# Amplificador_Logaritmo.net
KiCad netlist of a schematic drawn in EasyEDA Pro
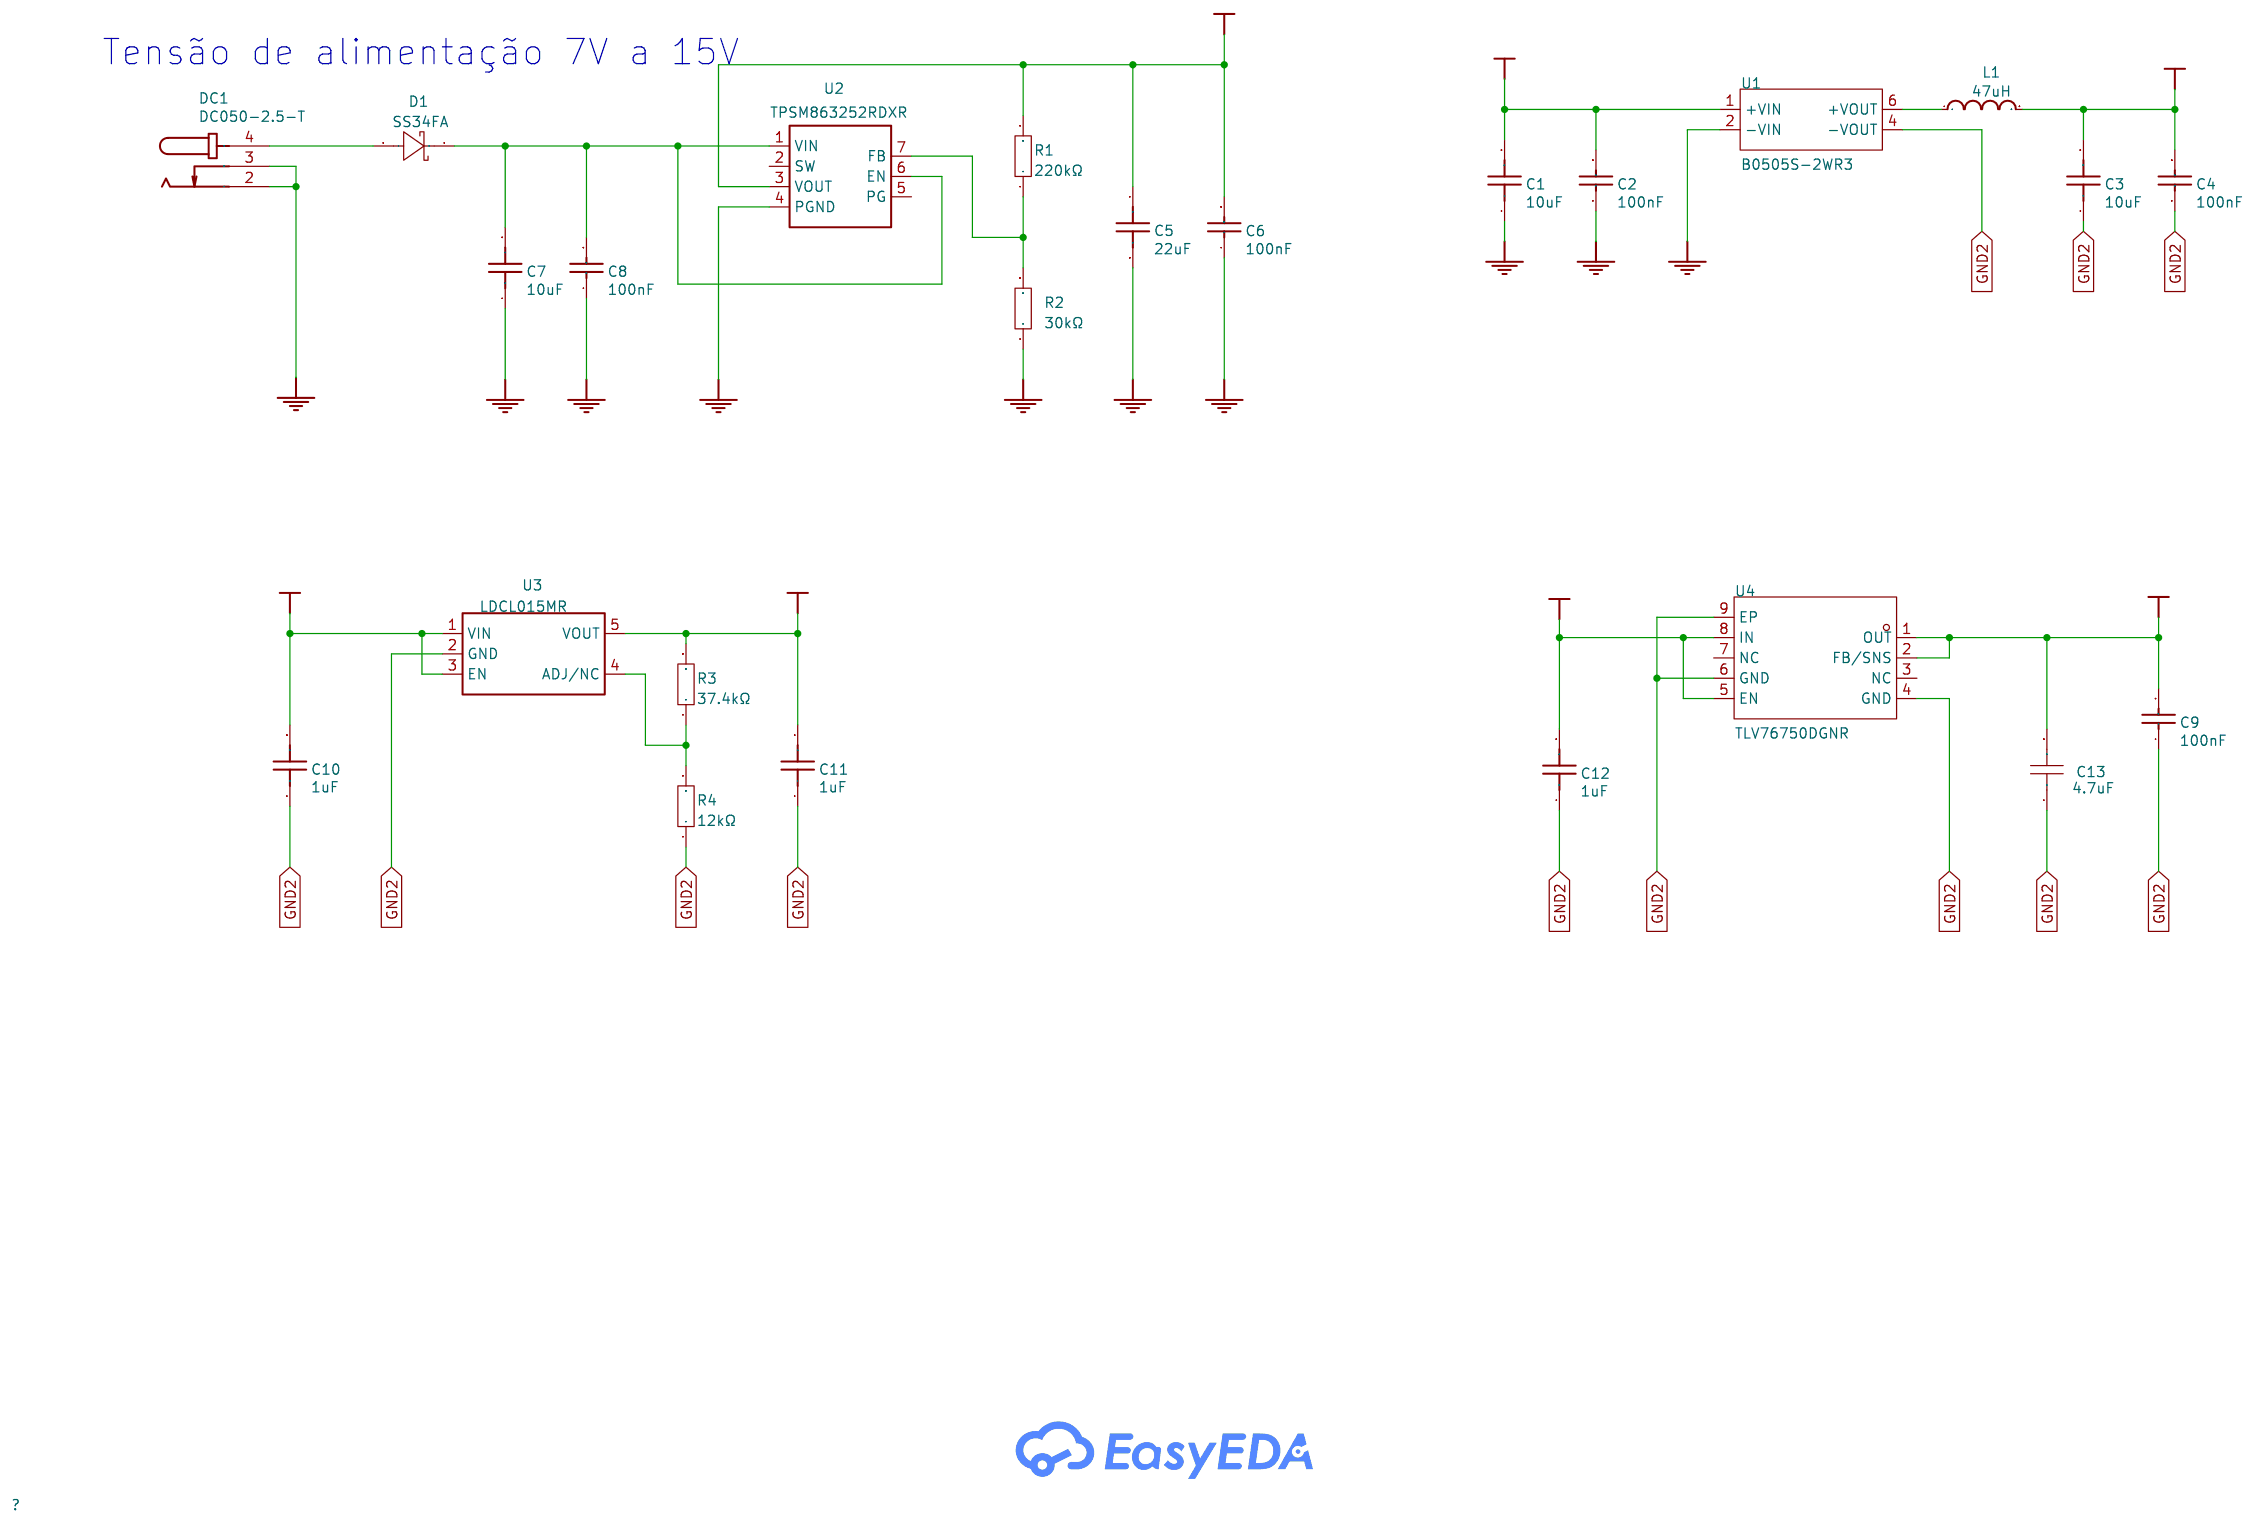
[diagram p0: Fontes]
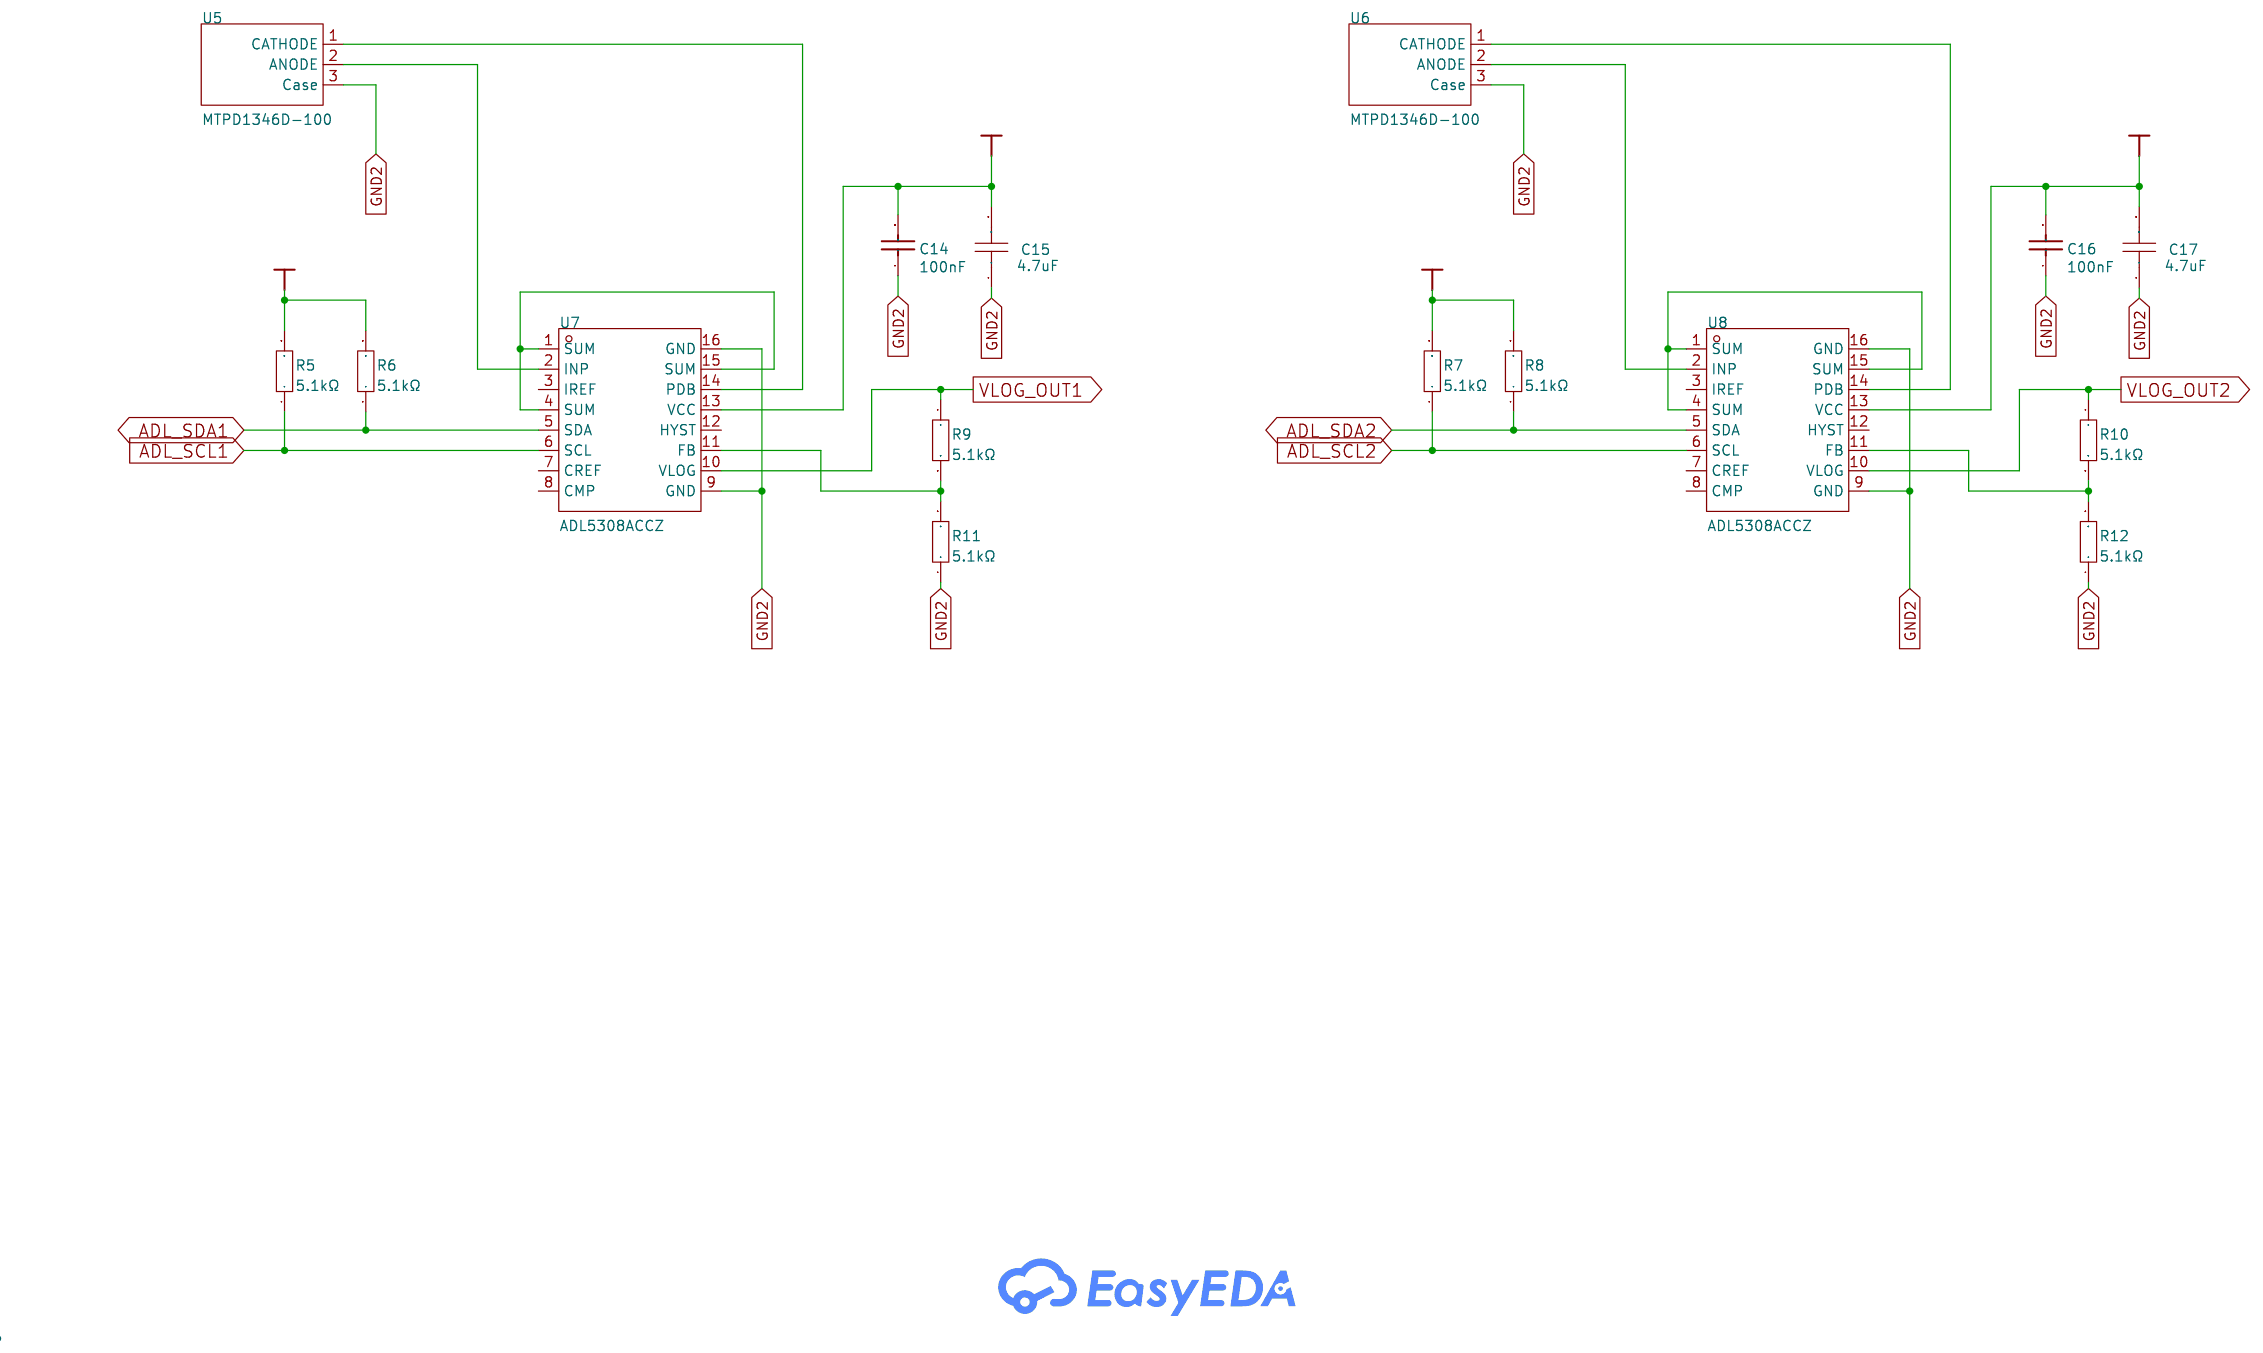
[diagram p1: Amplificador 1 e 2]
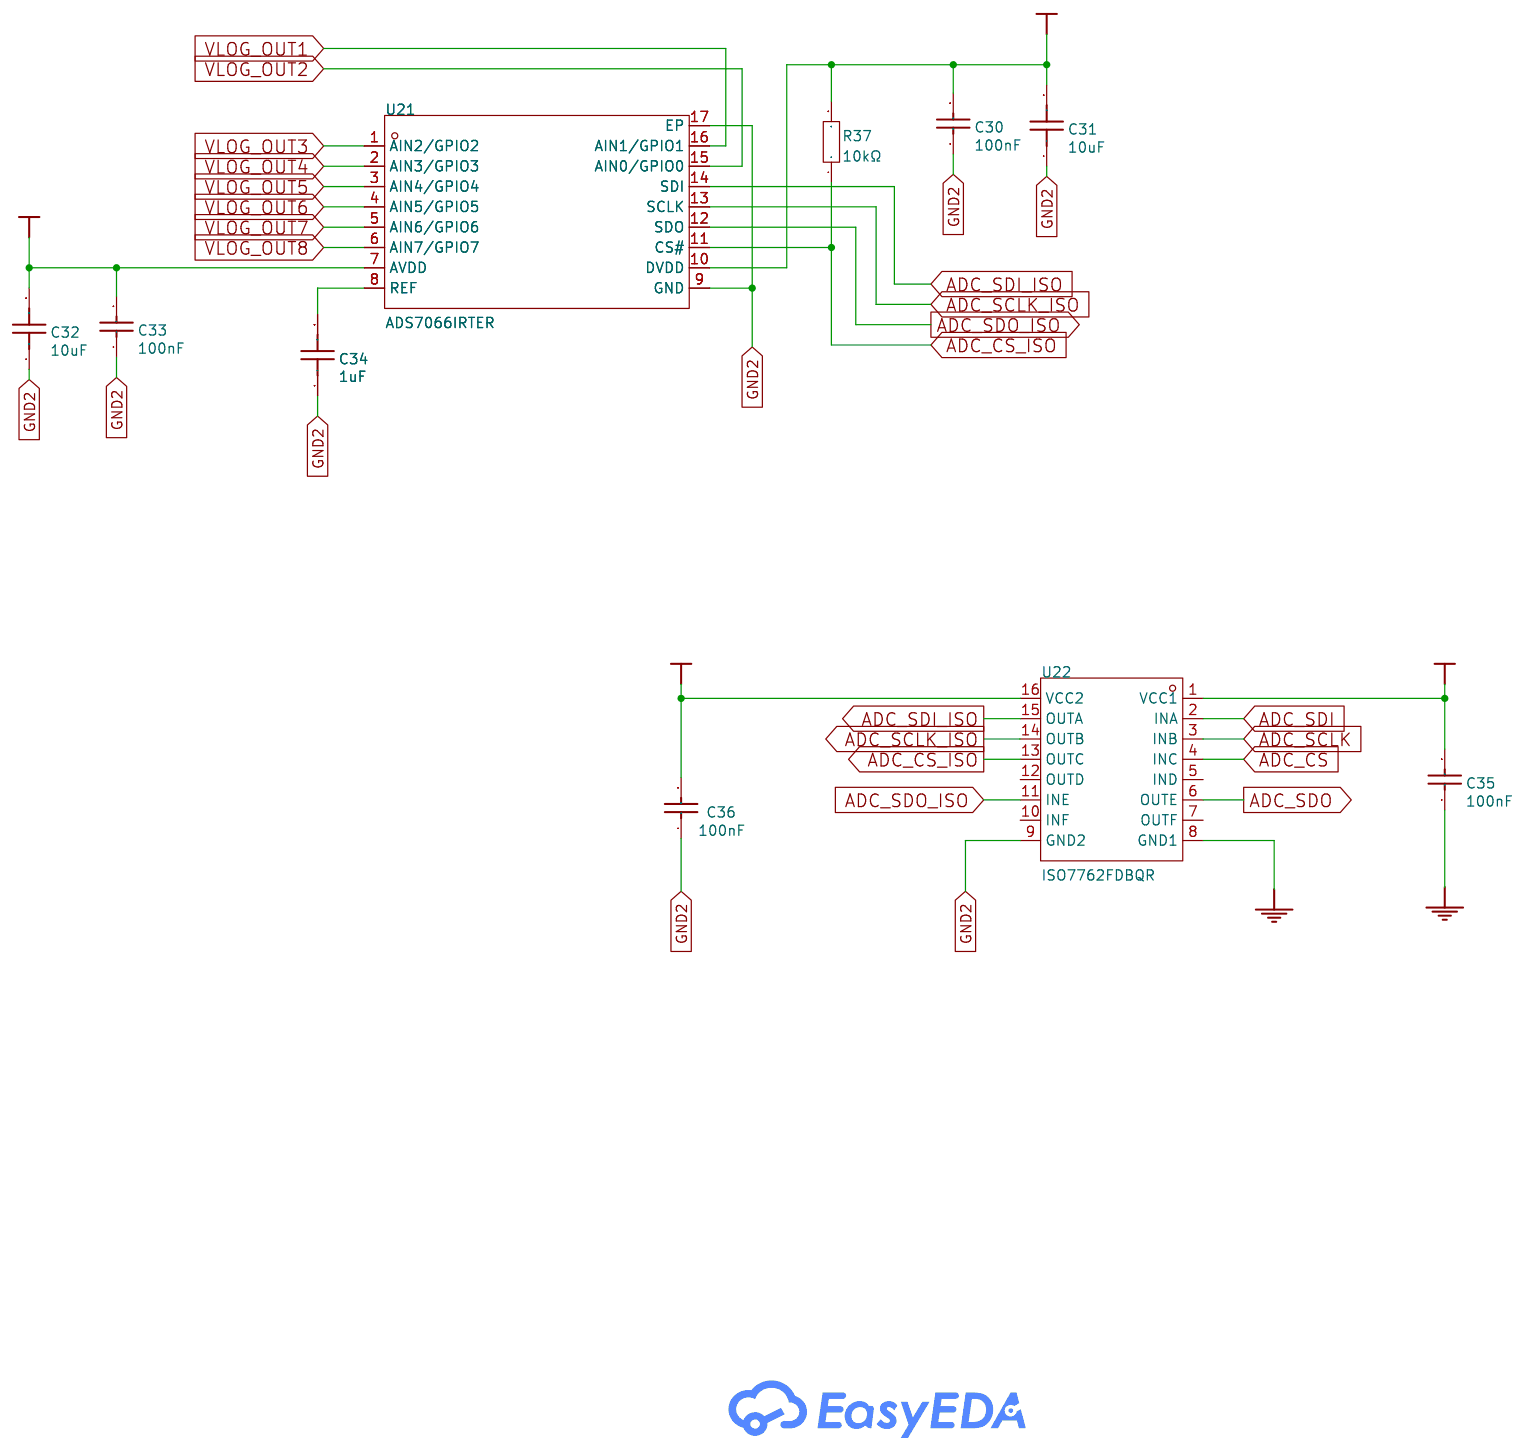
[diagram p2: ADC]
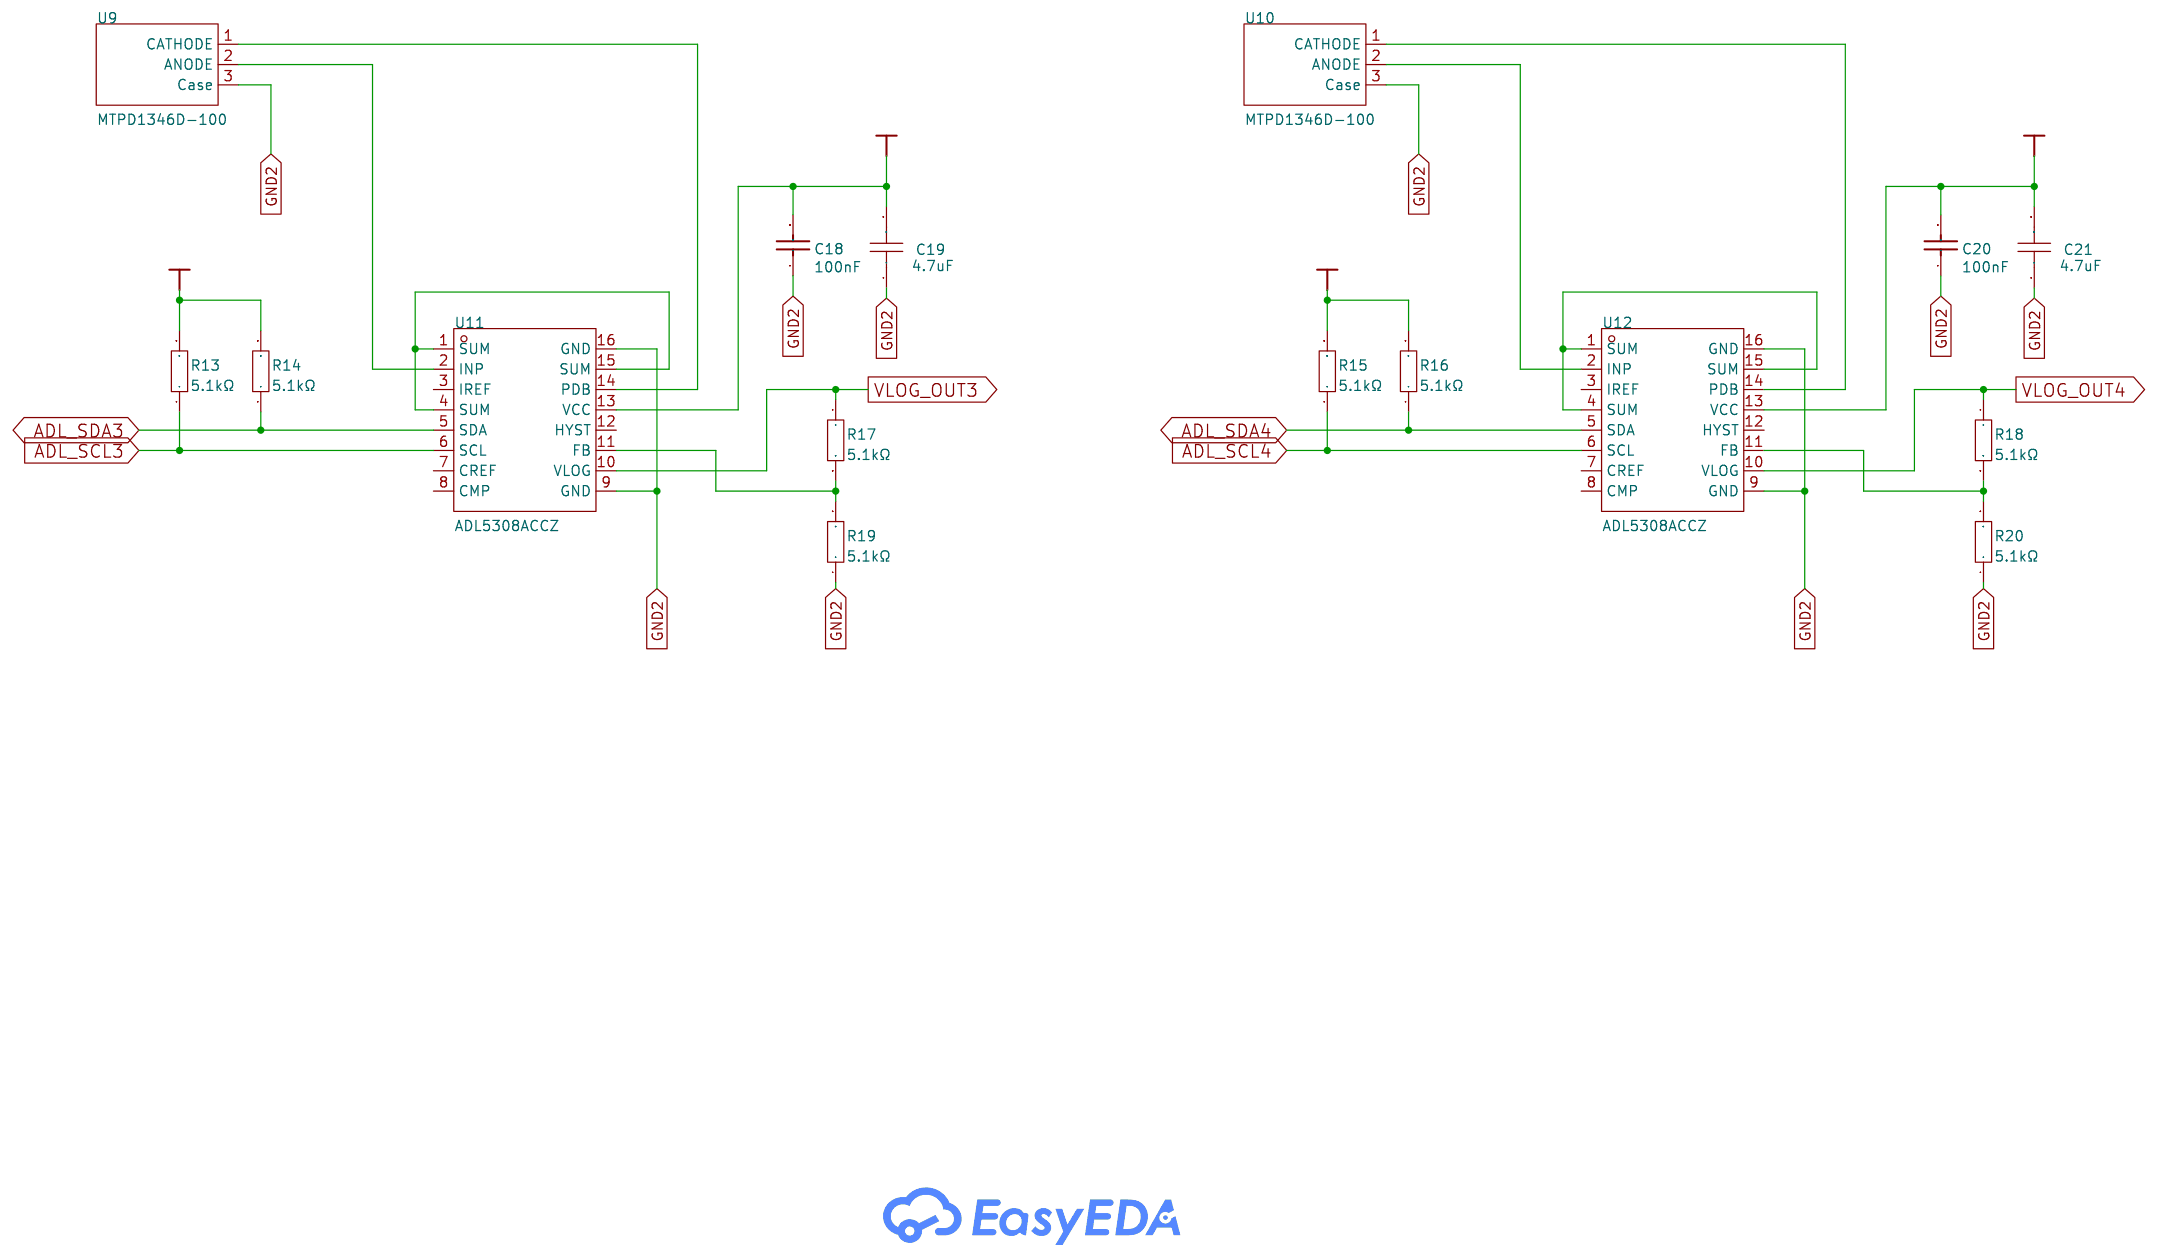
[diagram p3: Amplificador 3 e 4]
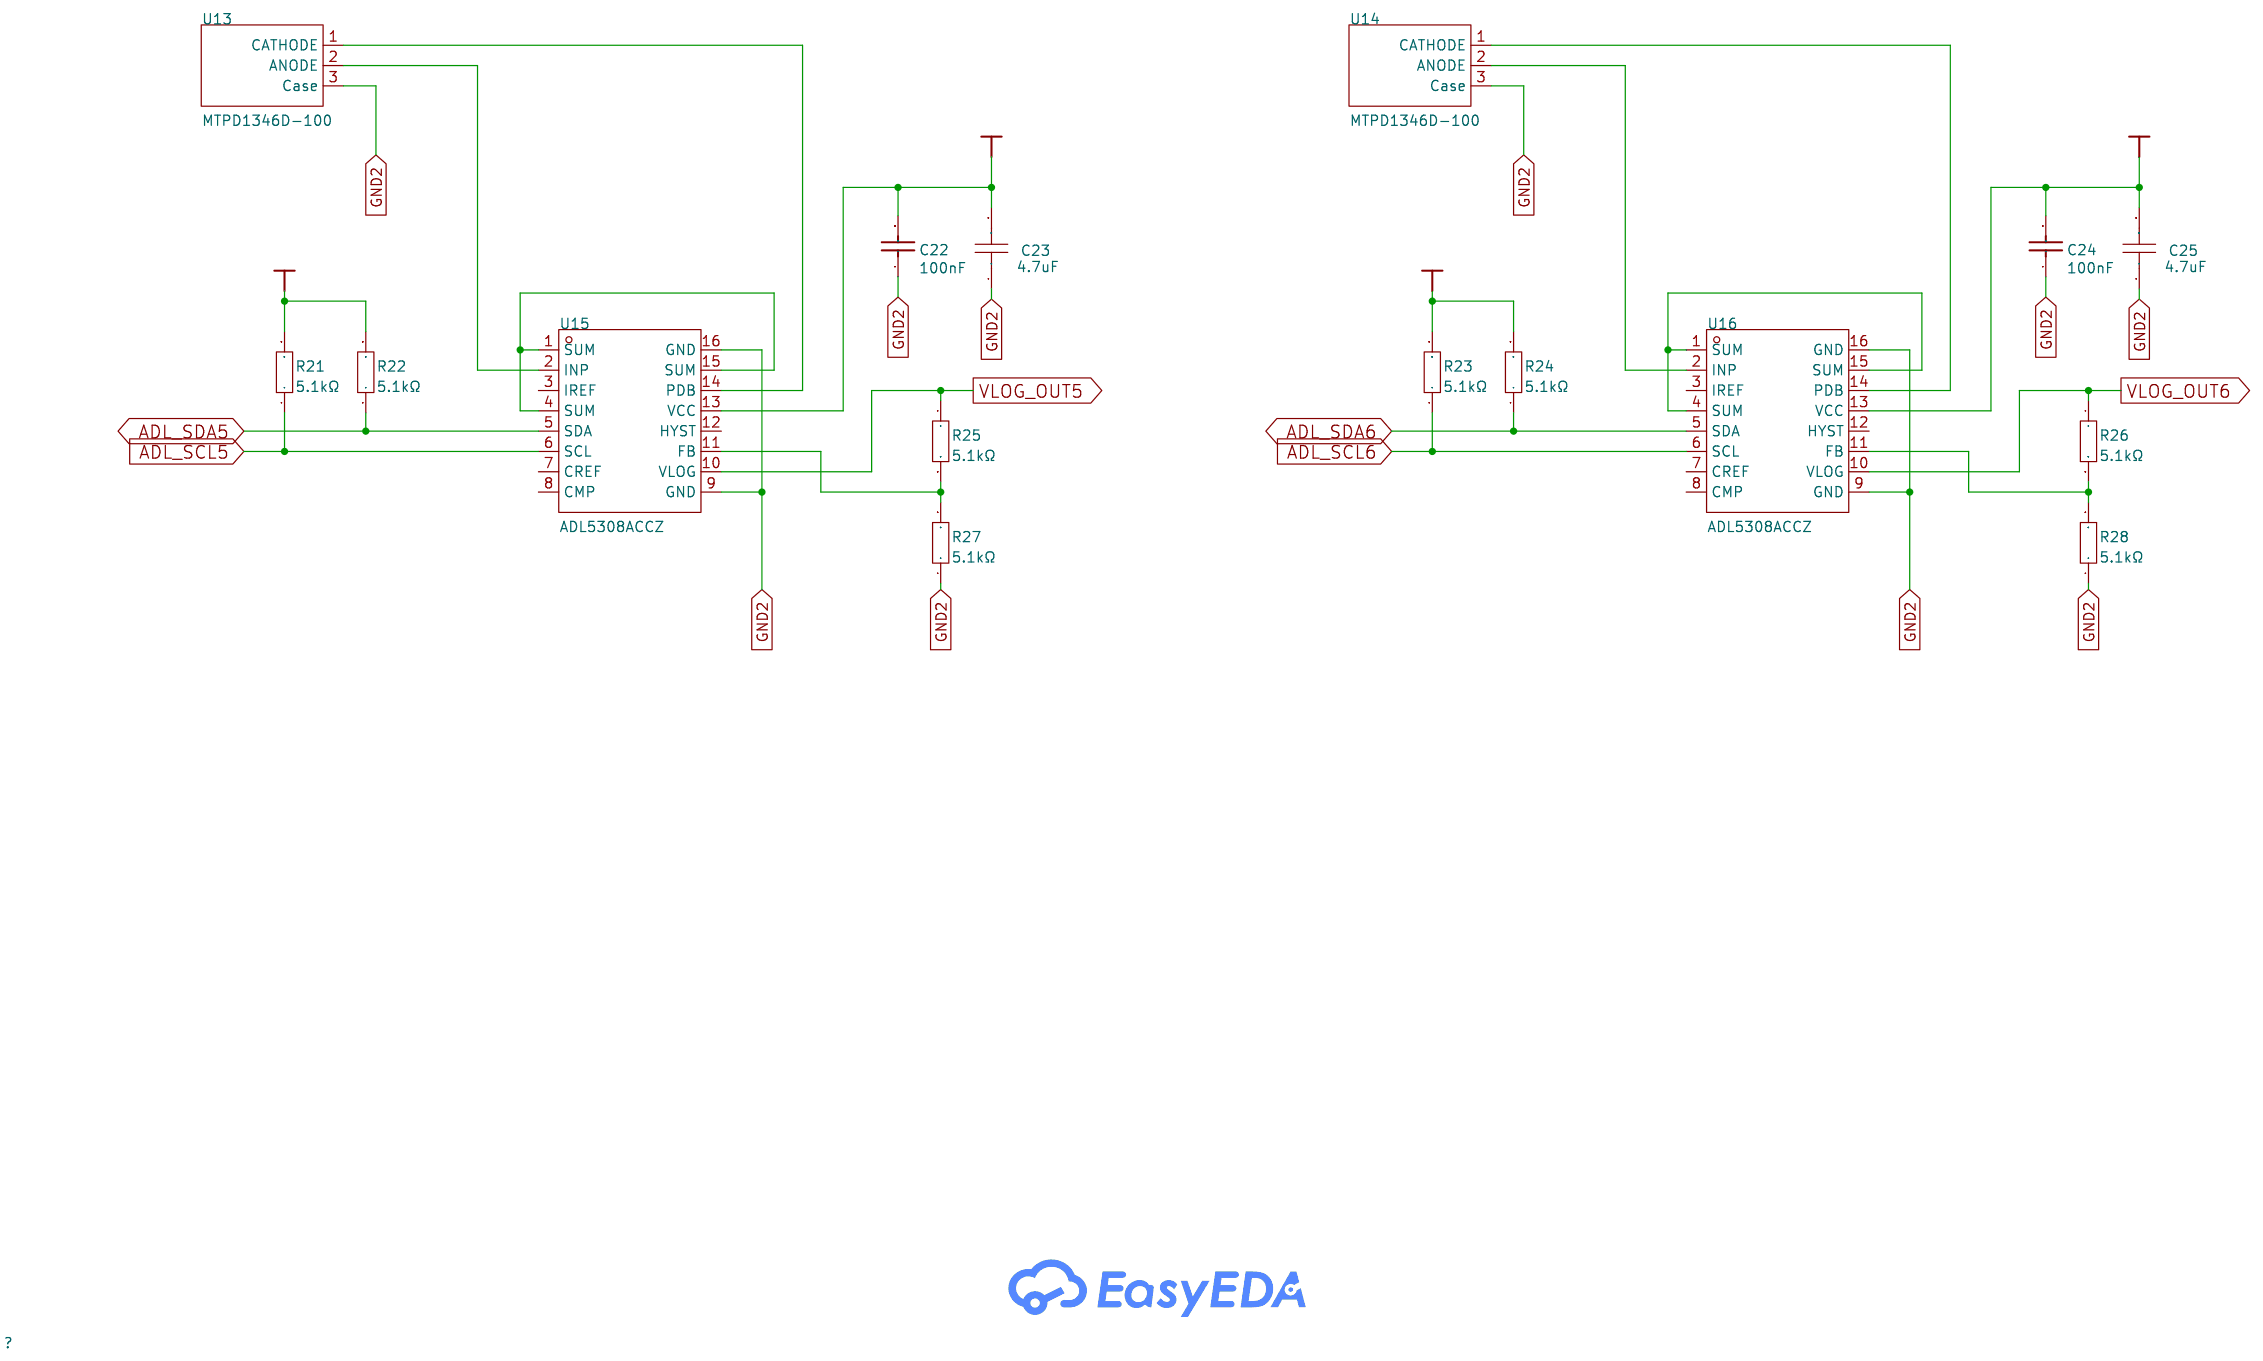
[diagram p4: Amplificador 5 e 6]
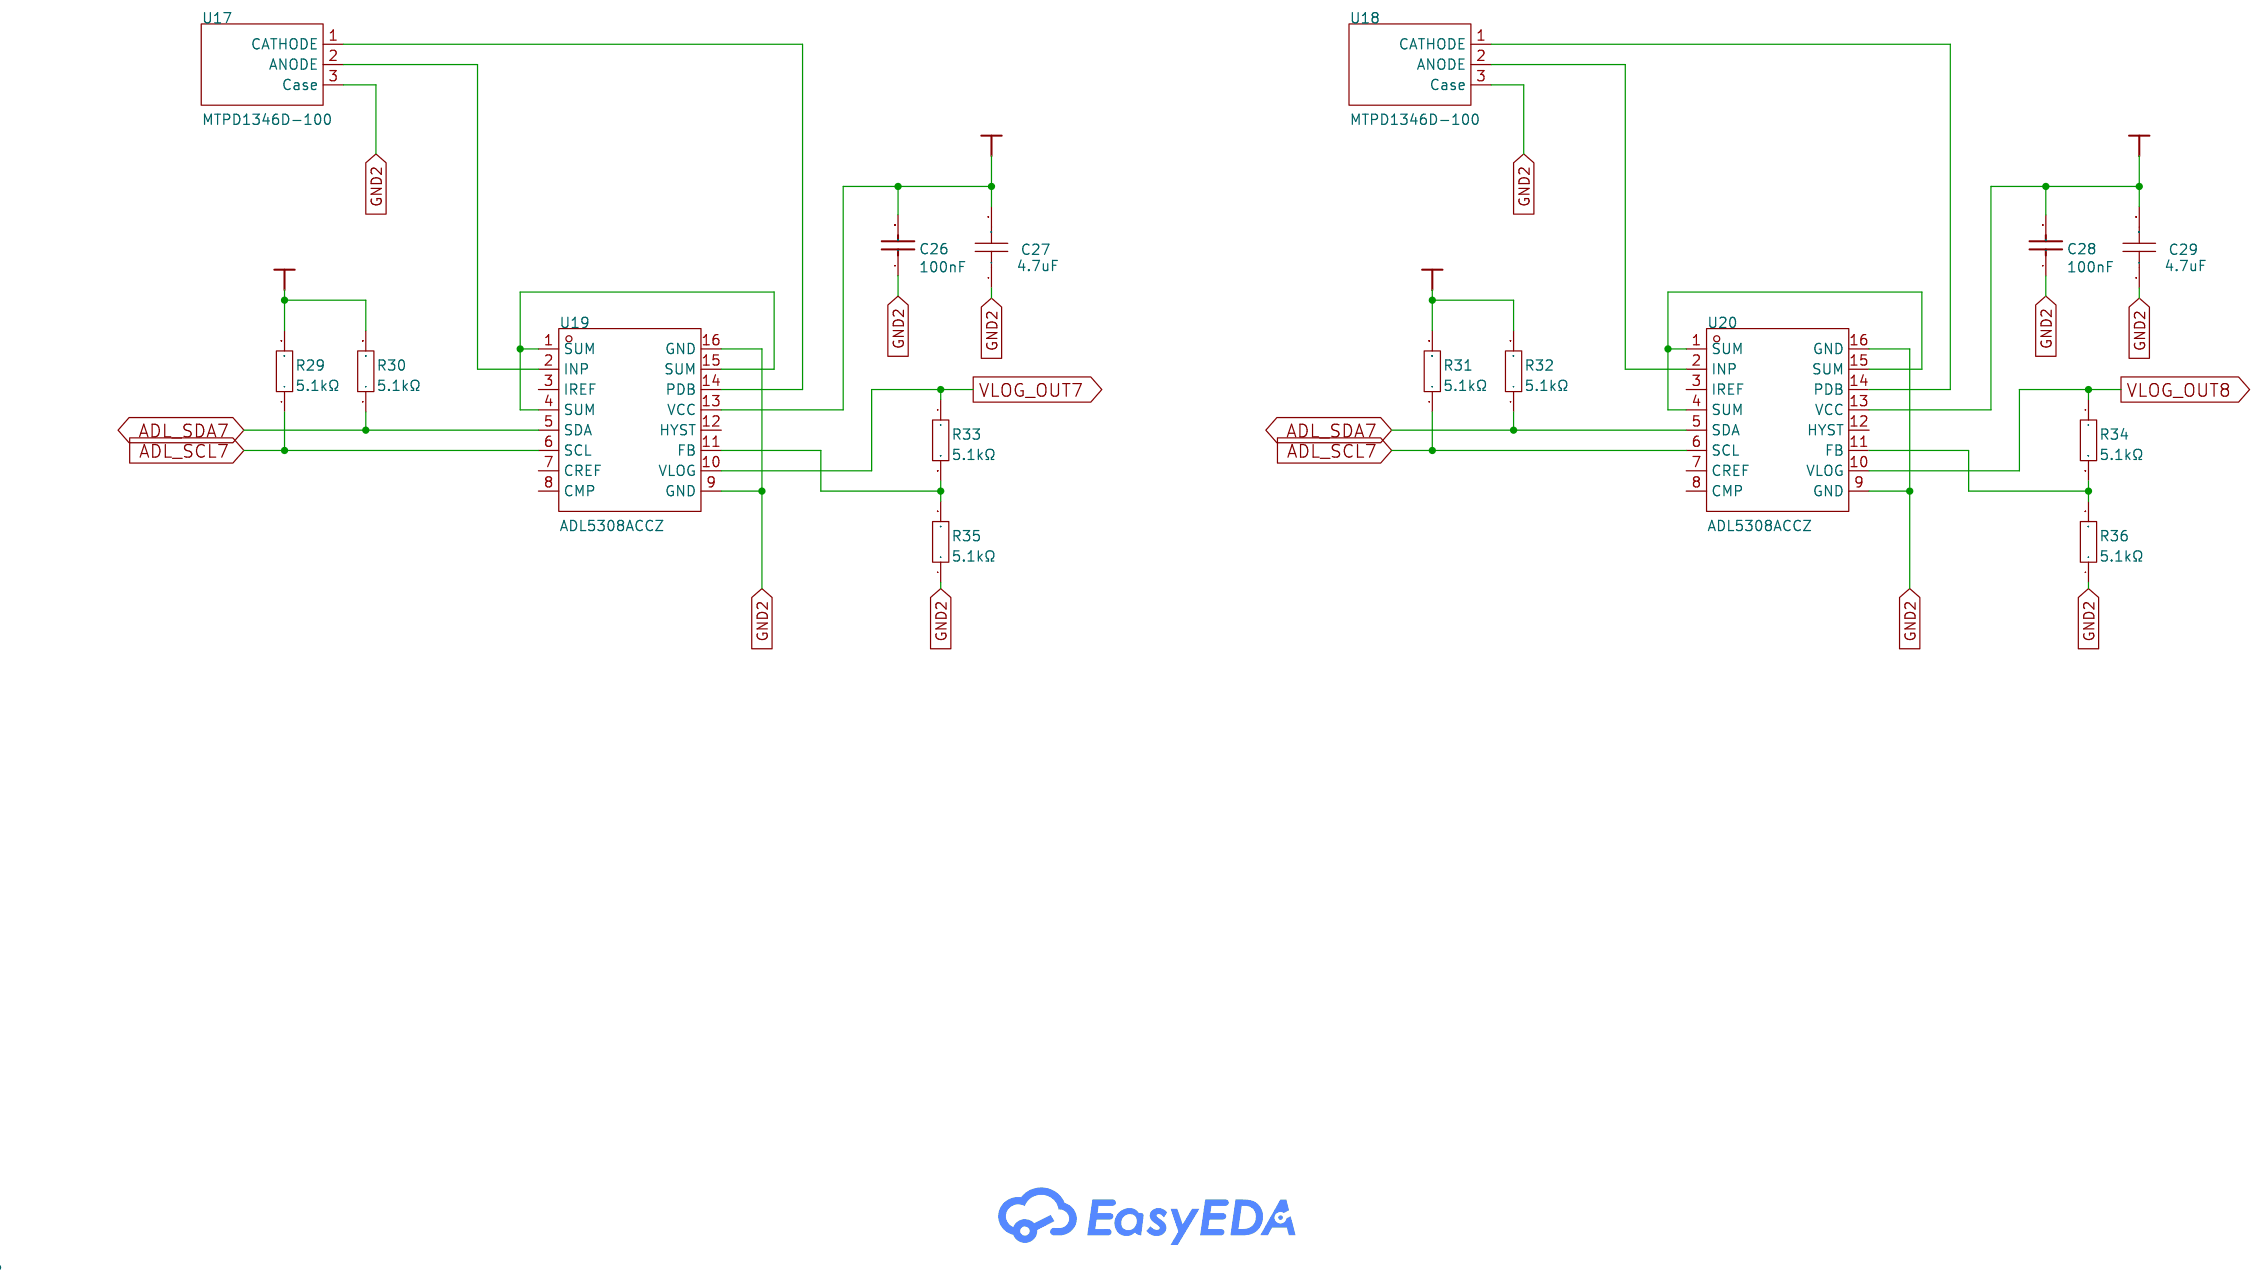
[diagram p5: Amplificador 7 e 8]
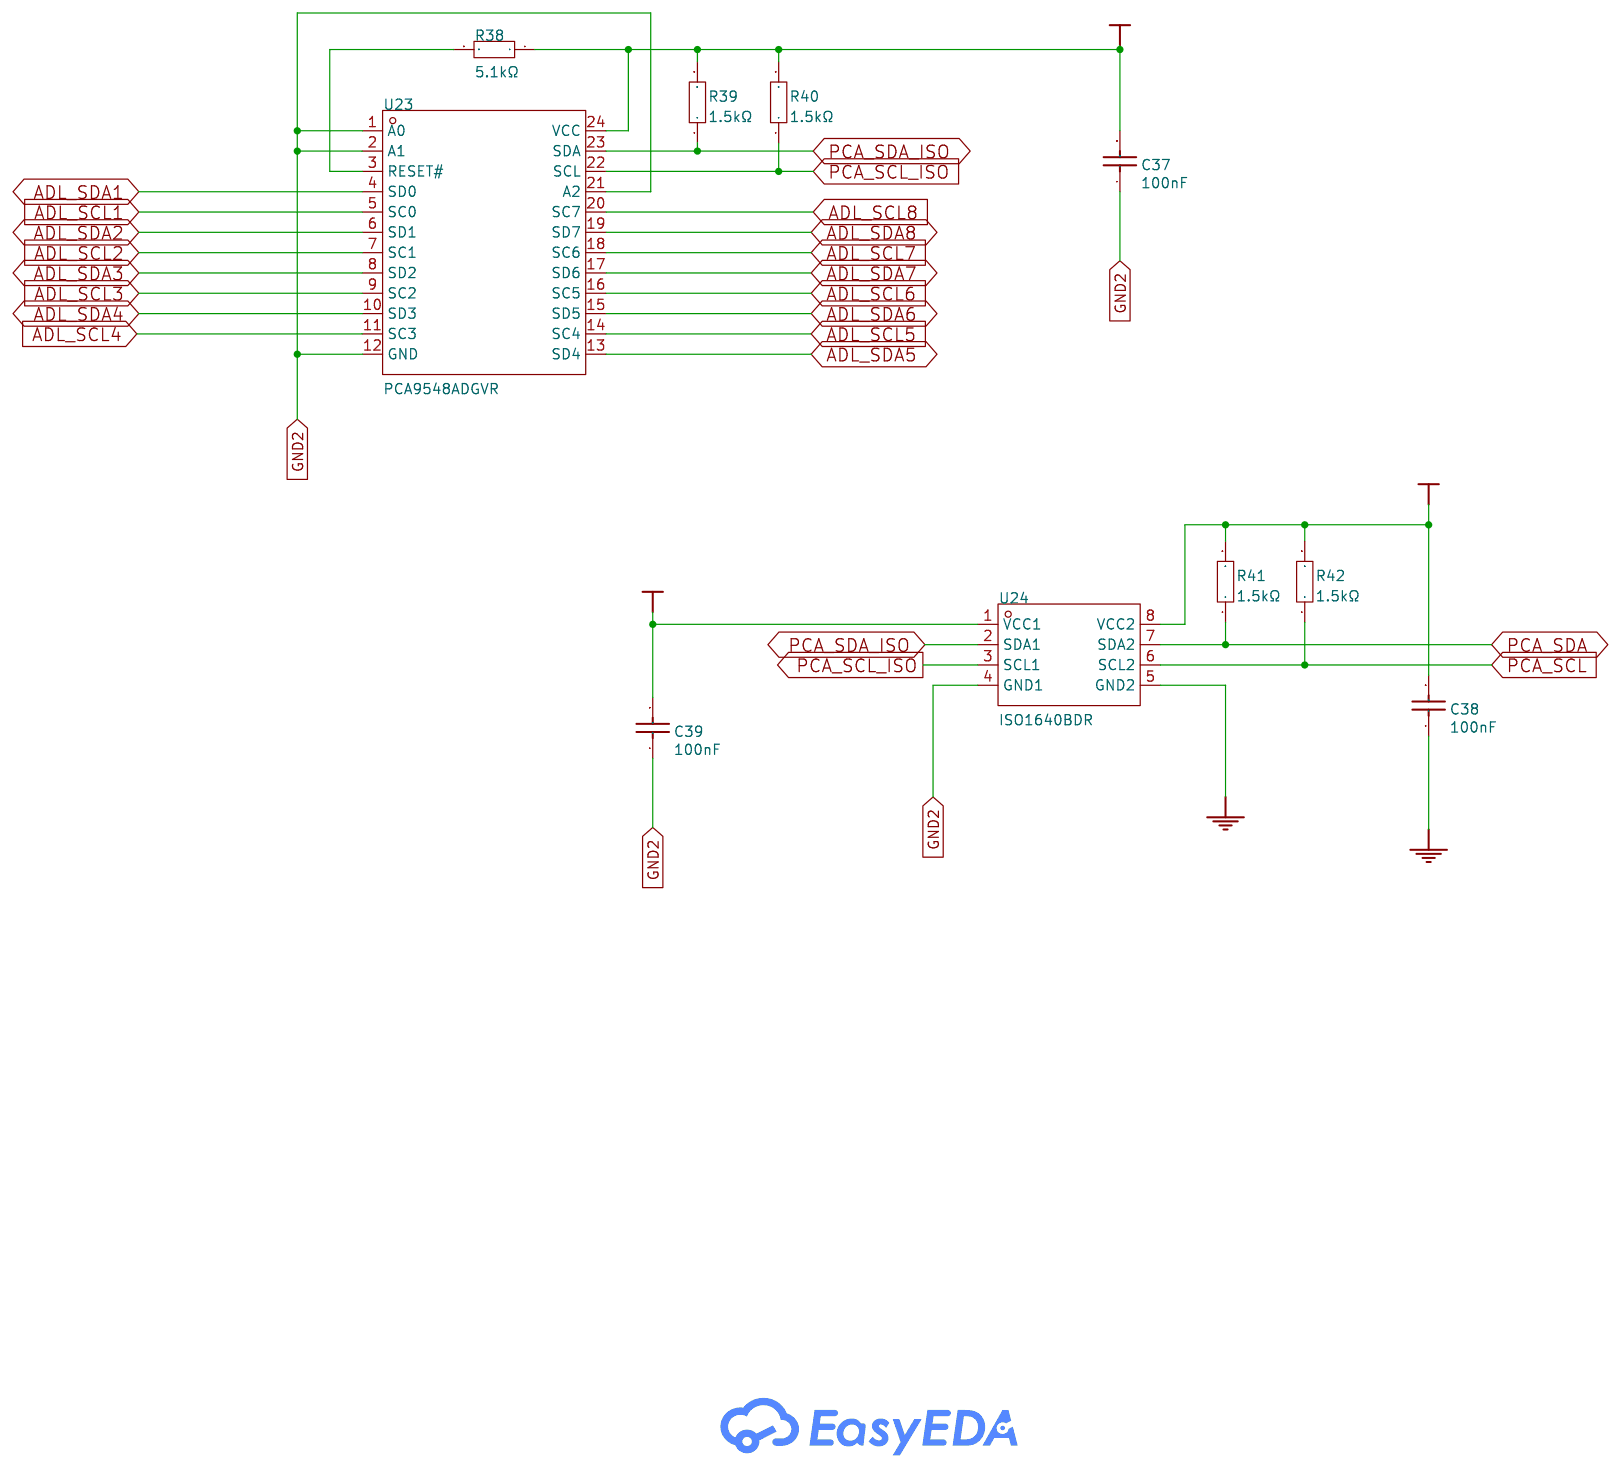
[diagram p6: Interface I2C]

(export (version "E")
  (design (tool "Eeschema 10.0.6"))
  (components
    (comp (ref "C1")
      (value "10uF")
      (description "Capacitance:10uF Tolerance:±20% Tolerance:±20% Voltage Rating:10V Temperature Coefficient:X5R")
      (libsource (lib "easyedapro") (part "10uF"))
    )
    (comp (ref "C2")
      (value "100nF")
      (fields (field (name "Manufacturer Part") "GCM155R71H104KE02D"))
      (libsource (lib "easyedapro") (part "100nF"))
    )
    (comp (ref "C3")
      (value "10uF")
      (description "Capacitance:10uF Tolerance:±20% Tolerance:±20% Voltage Rating:10V Temperature Coefficient:X5R")
      (libsource (lib "easyedapro") (part "10uF"))
    )
    (comp (ref "C4")
      (value "100nF")
      (fields (field (name "Manufacturer Part") "GCM155R71H104KE02D"))
      (libsource (lib "easyedapro") (part "100nF"))
    )
    (comp (ref "C5")
      (value "22uF")
      (fields (field (name "Manufacturer Part") "CL10A226MO7JZNC") (field (name "Contributor") "lcsc"))
      (libsource (lib "easyedapro") (part "22uF"))
    )
    (comp (ref "C6")
      (value "100nF")
      (fields (field (name "Manufacturer Part") "GCM155R71H104KE02D"))
      (libsource (lib "easyedapro") (part "100nF"))
    )
    (comp (ref "C7")
      (value "10uF")
      (fields
        (field (name "Manufacturer Part") "CL10A106MA8NRNC")
        (field (name "Manufacturer") "SAMSUNG(三星)")
      )
      (libsource (lib "easyedapro") (part "10uF"))
    )
    (comp (ref "C8")
      (value "100nF")
      (fields (field (name "Manufacturer Part") "GCM155R71H104KE02D"))
      (libsource (lib "easyedapro") (part "100nF"))
    )
    (comp (ref "C9")
      (value "100nF")
      (fields (field (name "Manufacturer Part") "GCM155R71H104KE02D"))
      (libsource (lib "easyedapro") (part "100nF"))
    )
    (comp (ref "C10")
      (value "1uF")
      (fields (field (name "Manufacturer Part") "GRM155Z71A105KE01D") (field (name "Contributor") "LCSC"))
      (libsource (lib "easyedapro") (part "1uF"))
    )
    (comp (ref "C11")
      (value "1uF")
      (fields (field (name "Manufacturer Part") "GRM155Z71A105KE01D") (field (name "Contributor") "LCSC"))
      (libsource (lib "easyedapro") (part "1uF"))
    )
    (comp (ref "C12")
      (value "1uF")
      (fields (field (name "Manufacturer Part") "GRM155Z71A105KE01D") (field (name "Contributor") "LCSC"))
      (libsource (lib "easyedapro") (part "1uF"))
    )
    (comp (ref "C13")
      (value "4.7uF")
      (footprint "easyedapro:C0402")
      (fields
        (field (name "Manufacturer Part") "GRM155R61A475MEAAD")
        (field (name "Manufacturer") "muRata(村田)")
      )
      (libsource (lib "easyedapro") (part "GRM155R61A475MEAAD"))
    )
    (comp (ref "D1")
      (value "SS34FA")
      (footprint "easyedapro:SOD-123FL_L2.8-W1.8-LS3.6-RD")
      (fields (field (name "Manufacturer") "onsemi(安森美)"))
      (libsource (lib "easyedapro") (part "SS34FA"))
    )
    (comp (ref "DC1")
      (value "DC050-2.5-T")
      (footprint "easyedapro:DC-IN-SMD_HX-DC050-2.5-T")
      (fields (field (name "Manufacturer") "SHOU HAN(首韩)") (field (name "Contributor") "lcsc"))
      (libsource (lib "easyedapro") (part "DC050-2.5-T"))
    )
    (comp (ref "L1")
      (value "47uH")
      (footprint "easyedapro:IND-SMD_L3.2-W2.5-BRL3225T100M")
      (fields
        (field (name "Manufacturer Part") "BRL3225T470K")
        (field (name "Manufacturer") "TAIYO YUDEN(太诱)")
        (field (name "Contributor") "LCSC")
      )
      (libsource (lib "easyedapro") (part "47uH"))
    )
    (comp (ref "R1")
      (value "220kΩ")
      (footprint "easyedapro:R0402")
      (fields (field (name "Manufacturer Part") "RC0402FR-07220KL") (field (name "Manufacturer") "YAGEO(国巨)"))
      (libsource (lib "easyedapro") (part "RC0402FR-07220KL"))
    )
    (comp (ref "R2")
      (value "30kΩ")
      (footprint "easyedapro:R0402")
      (fields (field (name "Manufacturer Part") "RC0402FR-0730KL") (field (name "Manufacturer") "YAGEO(国巨)"))
      (libsource (lib "easyedapro") (part "RC0402FR-0730KL"))
    )
    (comp (ref "R3")
      (value "37.4kΩ")
      (footprint "easyedapro:R0402")
      (fields (field (name "Manufacturer Part") "AC0402FR-0737K4L") (field (name "Manufacturer") "YAGEO(国巨)"))
      (libsource (lib "easyedapro") (part "AC0402FR-0737K4L"))
    )
    (comp (ref "R4")
      (value "12kΩ")
      (footprint "easyedapro:R0402")
      (fields (field (name "Manufacturer Part") "RC0402FR-0712KL") (field (name "Manufacturer") "YAGEO(国巨)"))
      (libsource (lib "easyedapro") (part "RC0402FR-0712KL"))
    )
    (comp (ref "U1")
      (value "B0505S-2WR3")
      (footprint "easyedapro:PWRM-TH_IBXX05S-2WR3")
      (fields (field (name "Manufacturer") "HI-LINK(海凌科)"))
      (libsource (lib "easyedapro") (part "B0505S-2WR3_C5365300"))
    )
    (comp (ref "U2")
      (value "TPSM863252RDXR")
      (footprint "easyedapro:QFN-7_L4.0-W3.3_TPSM863257RDXR")
      (fields (field (name "Manufacturer") "TI(德州仪器)") (field (name "Contributor") "lcsc"))
      (libsource (lib "easyedapro") (part "TPSM863252RDXR"))
    )
    (comp (ref "U3")
      (value "LDCL015MR")
      (footprint "easyedapro:SOT-23-5_L3.0-W1.6-P0.95-LS2.8-BL")
      (fields (field (name "Manufacturer") "ST(意法半导体)") (field (name "Contributor") "LCSC"))
      (libsource (lib "easyedapro") (part "LDCL015MR"))
    )
    (comp (ref "U4")
      (value "TLV76750DGNR")
      (footprint "easyedapro:HVSSOP-8_L3.0-W3.0-P0.65-LS4.9-BL-EP2.1")
      (fields (field (name "Manufacturer") "TI(德州仪器)"))
      (libsource (lib "easyedapro") (part "TLV76750DGNR"))
    )
    (comp (ref "C14")
      (value "100nF")
      (fields (field (name "Manufacturer Part") "GCM155R71H104KE02D"))
      (libsource (lib "easyedapro") (part "100nF"))
    )
    (comp (ref "C15")
      (value "4.7uF")
      (footprint "easyedapro:C0402")
      (fields
        (field (name "Manufacturer Part") "GRM155R61A475MEAAD")
        (field (name "Manufacturer") "muRata(村田)")
      )
      (libsource (lib "easyedapro") (part "GRM155R61A475MEAAD"))
    )
    (comp (ref "C16")
      (value "100nF")
      (fields (field (name "Manufacturer Part") "GCM155R71H104KE02D"))
      (libsource (lib "easyedapro") (part "100nF"))
    )
    (comp (ref "C17")
      (value "4.7uF")
      (footprint "easyedapro:C0402")
      (fields
        (field (name "Manufacturer Part") "GRM155R61A475MEAAD")
        (field (name "Manufacturer") "muRata(村田)")
      )
      (libsource (lib "easyedapro") (part "GRM155R61A475MEAAD"))
    )
    (comp (ref "R5")
      (value "5.1kΩ")
      (footprint "easyedapro:R0402")
      (fields (field (name "Manufacturer Part") "RC0402FR-075K1L") (field (name "Manufacturer") "YAGEO(国巨)"))
      (libsource (lib "easyedapro") (part "RC0402FR-075K1L"))
    )
    (comp (ref "R6")
      (value "5.1kΩ")
      (footprint "easyedapro:R0402")
      (fields (field (name "Manufacturer Part") "RC0402FR-075K1L") (field (name "Manufacturer") "YAGEO(国巨)"))
      (libsource (lib "easyedapro") (part "RC0402FR-075K1L"))
    )
    (comp (ref "R7")
      (value "5.1kΩ")
      (footprint "easyedapro:R0402")
      (fields (field (name "Manufacturer Part") "RC0402FR-075K1L") (field (name "Manufacturer") "YAGEO(国巨)"))
      (libsource (lib "easyedapro") (part "RC0402FR-075K1L"))
    )
    (comp (ref "R8")
      (value "5.1kΩ")
      (footprint "easyedapro:R0402")
      (fields (field (name "Manufacturer Part") "RC0402FR-075K1L") (field (name "Manufacturer") "YAGEO(国巨)"))
      (libsource (lib "easyedapro") (part "RC0402FR-075K1L"))
    )
    (comp (ref "R9")
      (value "5.1kΩ")
      (footprint "easyedapro:R0402")
      (fields (field (name "Manufacturer Part") "RC0402FR-075K1L") (field (name "Manufacturer") "YAGEO(国巨)"))
      (libsource (lib "easyedapro") (part "RC0402FR-075K1L"))
    )
    (comp (ref "R10")
      (value "5.1kΩ")
      (footprint "easyedapro:R0402")
      (fields (field (name "Manufacturer Part") "RC0402FR-075K1L") (field (name "Manufacturer") "YAGEO(国巨)"))
      (libsource (lib "easyedapro") (part "RC0402FR-075K1L"))
    )
    (comp (ref "R11")
      (value "5.1kΩ")
      (footprint "easyedapro:R0402")
      (fields (field (name "Manufacturer Part") "RC0402FR-075K1L") (field (name "Manufacturer") "YAGEO(国巨)"))
      (libsource (lib "easyedapro") (part "RC0402FR-075K1L"))
    )
    (comp (ref "R12")
      (value "5.1kΩ")
      (footprint "easyedapro:R0402")
      (fields (field (name "Manufacturer Part") "RC0402FR-075K1L") (field (name "Manufacturer") "YAGEO(国巨)"))
      (libsource (lib "easyedapro") (part "RC0402FR-075K1L"))
    )
    (comp (ref "U5")
      (value "MTPD1346D-100")
      (footprint "easyedapro:TO-46-3_BD5.4-P1.27-L")
      (fields (field (name "Manufacturer") "Marktech Optoelectronics"))
      (libsource (lib "easyedapro") (part "MTPD1346D-100"))
    )
    (comp (ref "U6")
      (value "MTPD1346D-100")
      (footprint "easyedapro:TO-46-3_BD5.4-P1.27-L")
      (fields (field (name "Manufacturer") "Marktech Optoelectronics"))
      (libsource (lib "easyedapro") (part "MTPD1346D-100"))
    )
    (comp (ref "U7")
      (value "ADL5308ACCZ")
      (footprint "easyedapro:LGA-14_L3.0-W2.0-P0.50-TL-EP")
      (fields (field (name "Manufacturer") "ADI(亚德诺)"))
      (libsource (lib "easyedapro") (part "ADL5308ACCZ"))
    )
    (comp (ref "U8")
      (value "ADL5308ACCZ")
      (footprint "easyedapro:LGA-14_L3.0-W2.0-P0.50-TL-EP")
      (fields (field (name "Manufacturer") "ADI(亚德诺)"))
      (libsource (lib "easyedapro") (part "ADL5308ACCZ"))
    )
    (comp (ref "C30")
      (value "100nF")
      (fields (field (name "Manufacturer Part") "GCM155R71H104KE02D"))
      (libsource (lib "easyedapro") (part "100nF"))
    )
    (comp (ref "C31")
      (value "10uF")
      (description "Capacitance:10uF Tolerance:±20% Tolerance:±20% Voltage Rating:10V Temperature Coefficient:X5R")
      (libsource (lib "easyedapro") (part "10uF"))
    )
    (comp (ref "C32")
      (value "10uF")
      (description "Capacitance:10uF Tolerance:±20% Tolerance:±20% Voltage Rating:10V Temperature Coefficient:X5R")
      (libsource (lib "easyedapro") (part "10uF"))
    )
    (comp (ref "C33")
      (value "100nF")
      (fields (field (name "Manufacturer Part") "GCM155R71H104KE02D"))
      (libsource (lib "easyedapro") (part "100nF"))
    )
    (comp (ref "C34")
      (value "1uF")
      (fields (field (name "Manufacturer Part") "GRM155Z71A105KE01D") (field (name "Contributor") "LCSC"))
      (libsource (lib "easyedapro") (part "1uF"))
    )
    (comp (ref "C35")
      (value "100nF")
      (fields (field (name "Manufacturer Part") "GCM155R71H104KE02D"))
      (libsource (lib "easyedapro") (part "100nF"))
    )
    (comp (ref "C36")
      (value "100nF")
      (fields (field (name "Manufacturer Part") "GCM155R71H104KE02D"))
      (libsource (lib "easyedapro") (part "100nF"))
    )
    (comp (ref "R37")
      (value "10kΩ")
      (footprint "easyedapro:R0402")
      (fields (field (name "Manufacturer Part") "RC0402FR-0710KL") (field (name "Manufacturer") "YAGEO(国巨)"))
      (libsource (lib "easyedapro") (part "RC0402FR-0710KL"))
    )
    (comp (ref "U21")
      (value "ADS7066IRTER")
      (footprint "easyedapro:WQFN-16_L3.0-W3.0-P0.50-TL-EP1.7")
      (fields (field (name "Manufacturer") "TI(德州仪器)"))
      (libsource (lib "easyedapro") (part "ADS7066IRTER"))
    )
    (comp (ref "U22")
      (value "ISO7762FDBQR")
      (footprint "easyedapro:SSOP-16_L4.9-W3.9-P0.64-LS6.0-BL")
      (fields (field (name "Manufacturer") "TI(德州仪器)"))
      (libsource (lib "easyedapro") (part "ISO7762FDBQR"))
    )
    (comp (ref "C18")
      (value "100nF")
      (fields (field (name "Manufacturer Part") "GCM155R71H104KE02D"))
      (libsource (lib "easyedapro") (part "100nF"))
    )
    (comp (ref "C19")
      (value "4.7uF")
      (footprint "easyedapro:C0402")
      (fields
        (field (name "Manufacturer Part") "GRM155R61A475MEAAD")
        (field (name "Manufacturer") "muRata(村田)")
      )
      (libsource (lib "easyedapro") (part "GRM155R61A475MEAAD"))
    )
    (comp (ref "C20")
      (value "100nF")
      (fields (field (name "Manufacturer Part") "GCM155R71H104KE02D"))
      (libsource (lib "easyedapro") (part "100nF"))
    )
    (comp (ref "C21")
      (value "4.7uF")
      (footprint "easyedapro:C0402")
      (fields
        (field (name "Manufacturer Part") "GRM155R61A475MEAAD")
        (field (name "Manufacturer") "muRata(村田)")
      )
      (libsource (lib "easyedapro") (part "GRM155R61A475MEAAD"))
    )
    (comp (ref "R13")
      (value "5.1kΩ")
      (footprint "easyedapro:R0402")
      (fields (field (name "Manufacturer Part") "RC0402FR-075K1L") (field (name "Manufacturer") "YAGEO(国巨)"))
      (libsource (lib "easyedapro") (part "RC0402FR-075K1L"))
    )
    (comp (ref "R14")
      (value "5.1kΩ")
      (footprint "easyedapro:R0402")
      (fields (field (name "Manufacturer Part") "RC0402FR-075K1L") (field (name "Manufacturer") "YAGEO(国巨)"))
      (libsource (lib "easyedapro") (part "RC0402FR-075K1L"))
    )
    (comp (ref "R15")
      (value "5.1kΩ")
      (footprint "easyedapro:R0402")
      (fields (field (name "Manufacturer Part") "RC0402FR-075K1L") (field (name "Manufacturer") "YAGEO(国巨)"))
      (libsource (lib "easyedapro") (part "RC0402FR-075K1L"))
    )
    (comp (ref "R16")
      (value "5.1kΩ")
      (footprint "easyedapro:R0402")
      (fields (field (name "Manufacturer Part") "RC0402FR-075K1L") (field (name "Manufacturer") "YAGEO(国巨)"))
      (libsource (lib "easyedapro") (part "RC0402FR-075K1L"))
    )
    (comp (ref "R17")
      (value "5.1kΩ")
      (footprint "easyedapro:R0402")
      (fields (field (name "Manufacturer Part") "RC0402FR-075K1L") (field (name "Manufacturer") "YAGEO(国巨)"))
      (libsource (lib "easyedapro") (part "RC0402FR-075K1L"))
    )
    (comp (ref "R18")
      (value "5.1kΩ")
      (footprint "easyedapro:R0402")
      (fields (field (name "Manufacturer Part") "RC0402FR-075K1L") (field (name "Manufacturer") "YAGEO(国巨)"))
      (libsource (lib "easyedapro") (part "RC0402FR-075K1L"))
    )
    (comp (ref "R19")
      (value "5.1kΩ")
      (footprint "easyedapro:R0402")
      (fields (field (name "Manufacturer Part") "RC0402FR-075K1L") (field (name "Manufacturer") "YAGEO(国巨)"))
      (libsource (lib "easyedapro") (part "RC0402FR-075K1L"))
    )
    (comp (ref "R20")
      (value "5.1kΩ")
      (footprint "easyedapro:R0402")
      (fields (field (name "Manufacturer Part") "RC0402FR-075K1L") (field (name "Manufacturer") "YAGEO(国巨)"))
      (libsource (lib "easyedapro") (part "RC0402FR-075K1L"))
    )
    (comp (ref "U9")
      (value "MTPD1346D-100")
      (footprint "easyedapro:TO-46-3_BD5.4-P1.27-L")
      (fields (field (name "Manufacturer") "Marktech Optoelectronics"))
      (libsource (lib "easyedapro") (part "MTPD1346D-100"))
    )
    (comp (ref "U10")
      (value "MTPD1346D-100")
      (footprint "easyedapro:TO-46-3_BD5.4-P1.27-L")
      (fields (field (name "Manufacturer") "Marktech Optoelectronics"))
      (libsource (lib "easyedapro") (part "MTPD1346D-100"))
    )
    (comp (ref "U11")
      (value "ADL5308ACCZ")
      (footprint "easyedapro:LGA-14_L3.0-W2.0-P0.50-TL-EP")
      (fields (field (name "Manufacturer") "ADI(亚德诺)"))
      (libsource (lib "easyedapro") (part "ADL5308ACCZ"))
    )
    (comp (ref "U12")
      (value "ADL5308ACCZ")
      (footprint "easyedapro:LGA-14_L3.0-W2.0-P0.50-TL-EP")
      (fields (field (name "Manufacturer") "ADI(亚德诺)"))
      (libsource (lib "easyedapro") (part "ADL5308ACCZ"))
    )
    (comp (ref "C22")
      (value "100nF")
      (fields (field (name "Manufacturer Part") "GCM155R71H104KE02D"))
      (libsource (lib "easyedapro") (part "100nF"))
    )
    (comp (ref "C23")
      (value "4.7uF")
      (footprint "easyedapro:C0402")
      (fields
        (field (name "Manufacturer Part") "GRM155R61A475MEAAD")
        (field (name "Manufacturer") "muRata(村田)")
      )
      (libsource (lib "easyedapro") (part "GRM155R61A475MEAAD"))
    )
    (comp (ref "C24")
      (value "100nF")
      (fields (field (name "Manufacturer Part") "GCM155R71H104KE02D"))
      (libsource (lib "easyedapro") (part "100nF"))
    )
    (comp (ref "C25")
      (value "4.7uF")
      (footprint "easyedapro:C0402")
      (fields
        (field (name "Manufacturer Part") "GRM155R61A475MEAAD")
        (field (name "Manufacturer") "muRata(村田)")
      )
      (libsource (lib "easyedapro") (part "GRM155R61A475MEAAD"))
    )
    (comp (ref "R21")
      (value "5.1kΩ")
      (footprint "easyedapro:R0402")
      (fields (field (name "Manufacturer Part") "RC0402FR-075K1L") (field (name "Manufacturer") "YAGEO(国巨)"))
      (libsource (lib "easyedapro") (part "RC0402FR-075K1L"))
    )
    (comp (ref "R22")
      (value "5.1kΩ")
      (footprint "easyedapro:R0402")
      (fields (field (name "Manufacturer Part") "RC0402FR-075K1L") (field (name "Manufacturer") "YAGEO(国巨)"))
      (libsource (lib "easyedapro") (part "RC0402FR-075K1L"))
    )
    (comp (ref "R23")
      (value "5.1kΩ")
      (footprint "easyedapro:R0402")
      (fields (field (name "Manufacturer Part") "RC0402FR-075K1L") (field (name "Manufacturer") "YAGEO(国巨)"))
      (libsource (lib "easyedapro") (part "RC0402FR-075K1L"))
    )
    (comp (ref "R24")
      (value "5.1kΩ")
      (footprint "easyedapro:R0402")
      (fields (field (name "Manufacturer Part") "RC0402FR-075K1L") (field (name "Manufacturer") "YAGEO(国巨)"))
      (libsource (lib "easyedapro") (part "RC0402FR-075K1L"))
    )
    (comp (ref "R25")
      (value "5.1kΩ")
      (footprint "easyedapro:R0402")
      (fields (field (name "Manufacturer Part") "RC0402FR-075K1L") (field (name "Manufacturer") "YAGEO(国巨)"))
      (libsource (lib "easyedapro") (part "RC0402FR-075K1L"))
    )
    (comp (ref "R26")
      (value "5.1kΩ")
      (footprint "easyedapro:R0402")
      (fields (field (name "Manufacturer Part") "RC0402FR-075K1L") (field (name "Manufacturer") "YAGEO(国巨)"))
      (libsource (lib "easyedapro") (part "RC0402FR-075K1L"))
    )
    (comp (ref "R27")
      (value "5.1kΩ")
      (footprint "easyedapro:R0402")
      (fields (field (name "Manufacturer Part") "RC0402FR-075K1L") (field (name "Manufacturer") "YAGEO(国巨)"))
      (libsource (lib "easyedapro") (part "RC0402FR-075K1L"))
    )
    (comp (ref "R28")
      (value "5.1kΩ")
      (footprint "easyedapro:R0402")
      (fields (field (name "Manufacturer Part") "RC0402FR-075K1L") (field (name "Manufacturer") "YAGEO(国巨)"))
      (libsource (lib "easyedapro") (part "RC0402FR-075K1L"))
    )
    (comp (ref "U13")
      (value "MTPD1346D-100")
      (footprint "easyedapro:TO-46-3_BD5.4-P1.27-L")
      (fields (field (name "Manufacturer") "Marktech Optoelectronics"))
      (libsource (lib "easyedapro") (part "MTPD1346D-100"))
    )
    (comp (ref "U14")
      (value "MTPD1346D-100")
      (footprint "easyedapro:TO-46-3_BD5.4-P1.27-L")
      (fields (field (name "Manufacturer") "Marktech Optoelectronics"))
      (libsource (lib "easyedapro") (part "MTPD1346D-100"))
    )
    (comp (ref "U15")
      (value "ADL5308ACCZ")
      (footprint "easyedapro:LGA-14_L3.0-W2.0-P0.50-TL-EP")
      (fields (field (name "Manufacturer") "ADI(亚德诺)"))
      (libsource (lib "easyedapro") (part "ADL5308ACCZ"))
    )
    (comp (ref "U16")
      (value "ADL5308ACCZ")
      (footprint "easyedapro:LGA-14_L3.0-W2.0-P0.50-TL-EP")
      (fields (field (name "Manufacturer") "ADI(亚德诺)"))
      (libsource (lib "easyedapro") (part "ADL5308ACCZ"))
    )
    (comp (ref "C26")
      (value "100nF")
      (fields (field (name "Manufacturer Part") "GCM155R71H104KE02D"))
      (libsource (lib "easyedapro") (part "100nF"))
    )
    (comp (ref "C27")
      (value "4.7uF")
      (footprint "easyedapro:C0402")
      (fields
        (field (name "Manufacturer Part") "GRM155R61A475MEAAD")
        (field (name "Manufacturer") "muRata(村田)")
      )
      (libsource (lib "easyedapro") (part "GRM155R61A475MEAAD"))
    )
    (comp (ref "C28")
      (value "100nF")
      (fields (field (name "Manufacturer Part") "GCM155R71H104KE02D"))
      (libsource (lib "easyedapro") (part "100nF"))
    )
    (comp (ref "C29")
      (value "4.7uF")
      (footprint "easyedapro:C0402")
      (fields
        (field (name "Manufacturer Part") "GRM155R61A475MEAAD")
        (field (name "Manufacturer") "muRata(村田)")
      )
      (libsource (lib "easyedapro") (part "GRM155R61A475MEAAD"))
    )
    (comp (ref "R29")
      (value "5.1kΩ")
      (footprint "easyedapro:R0402")
      (fields (field (name "Manufacturer Part") "RC0402FR-075K1L") (field (name "Manufacturer") "YAGEO(国巨)"))
      (libsource (lib "easyedapro") (part "RC0402FR-075K1L"))
    )
    (comp (ref "R30")
      (value "5.1kΩ")
      (footprint "easyedapro:R0402")
      (fields (field (name "Manufacturer Part") "RC0402FR-075K1L") (field (name "Manufacturer") "YAGEO(国巨)"))
      (libsource (lib "easyedapro") (part "RC0402FR-075K1L"))
    )
    (comp (ref "R31")
      (value "5.1kΩ")
      (footprint "easyedapro:R0402")
      (fields (field (name "Manufacturer Part") "RC0402FR-075K1L") (field (name "Manufacturer") "YAGEO(国巨)"))
      (libsource (lib "easyedapro") (part "RC0402FR-075K1L"))
    )
    (comp (ref "R32")
      (value "5.1kΩ")
      (footprint "easyedapro:R0402")
      (fields (field (name "Manufacturer Part") "RC0402FR-075K1L") (field (name "Manufacturer") "YAGEO(国巨)"))
      (libsource (lib "easyedapro") (part "RC0402FR-075K1L"))
    )
    (comp (ref "R33")
      (value "5.1kΩ")
      (footprint "easyedapro:R0402")
      (fields (field (name "Manufacturer Part") "RC0402FR-075K1L") (field (name "Manufacturer") "YAGEO(国巨)"))
      (libsource (lib "easyedapro") (part "RC0402FR-075K1L"))
    )
    (comp (ref "R34")
      (value "5.1kΩ")
      (footprint "easyedapro:R0402")
      (fields (field (name "Manufacturer Part") "RC0402FR-075K1L") (field (name "Manufacturer") "YAGEO(国巨)"))
      (libsource (lib "easyedapro") (part "RC0402FR-075K1L"))
    )
    (comp (ref "R35")
      (value "5.1kΩ")
      (footprint "easyedapro:R0402")
      (fields (field (name "Manufacturer Part") "RC0402FR-075K1L") (field (name "Manufacturer") "YAGEO(国巨)"))
      (libsource (lib "easyedapro") (part "RC0402FR-075K1L"))
    )
    (comp (ref "R36")
      (value "5.1kΩ")
      (footprint "easyedapro:R0402")
      (fields (field (name "Manufacturer Part") "RC0402FR-075K1L") (field (name "Manufacturer") "YAGEO(国巨)"))
      (libsource (lib "easyedapro") (part "RC0402FR-075K1L"))
    )
    (comp (ref "U17")
      (value "MTPD1346D-100")
      (footprint "easyedapro:TO-46-3_BD5.4-P1.27-L")
      (fields (field (name "Manufacturer") "Marktech Optoelectronics"))
      (libsource (lib "easyedapro") (part "MTPD1346D-100"))
    )
    (comp (ref "U18")
      (value "MTPD1346D-100")
      (footprint "easyedapro:TO-46-3_BD5.4-P1.27-L")
      (fields (field (name "Manufacturer") "Marktech Optoelectronics"))
      (libsource (lib "easyedapro") (part "MTPD1346D-100"))
    )
    (comp (ref "U19")
      (value "ADL5308ACCZ")
      (footprint "easyedapro:LGA-14_L3.0-W2.0-P0.50-TL-EP")
      (fields (field (name "Manufacturer") "ADI(亚德诺)"))
      (libsource (lib "easyedapro") (part "ADL5308ACCZ"))
    )
    (comp (ref "U20")
      (value "ADL5308ACCZ")
      (footprint "easyedapro:LGA-14_L3.0-W2.0-P0.50-TL-EP")
      (fields (field (name "Manufacturer") "ADI(亚德诺)"))
      (libsource (lib "easyedapro") (part "ADL5308ACCZ"))
    )
    (comp (ref "C37")
      (value "100nF")
      (fields (field (name "Manufacturer Part") "GCM155R71H104KE02D"))
      (libsource (lib "easyedapro") (part "100nF"))
    )
    (comp (ref "C38")
      (value "100nF")
      (fields (field (name "Manufacturer Part") "GCM155R71H104KE02D"))
      (libsource (lib "easyedapro") (part "100nF"))
    )
    (comp (ref "C39")
      (value "100nF")
      (fields (field (name "Manufacturer Part") "GCM155R71H104KE02D"))
      (libsource (lib "easyedapro") (part "100nF"))
    )
    (comp (ref "R38")
      (value "5.1kΩ")
      (footprint "easyedapro:R0402")
      (fields (field (name "Manufacturer Part") "RC0402FR-075K1L") (field (name "Manufacturer") "YAGEO(国巨)"))
      (libsource (lib "easyedapro") (part "RC0402FR-075K1L"))
    )
    (comp (ref "R39")
      (value "1.5kΩ")
      (footprint "easyedapro:R0402")
      (fields (field (name "Manufacturer Part") "RC0402FR-071K5L") (field (name "Manufacturer") "YAGEO(国巨)"))
      (libsource (lib "easyedapro") (part "RC0402FR-071K5L"))
    )
    (comp (ref "R40")
      (value "1.5kΩ")
      (footprint "easyedapro:R0402")
      (fields (field (name "Manufacturer Part") "RC0402FR-071K5L") (field (name "Manufacturer") "YAGEO(国巨)"))
      (libsource (lib "easyedapro") (part "RC0402FR-071K5L"))
    )
    (comp (ref "R41")
      (value "1.5kΩ")
      (footprint "easyedapro:R0402")
      (fields (field (name "Manufacturer Part") "RC0402FR-071K5L") (field (name "Manufacturer") "YAGEO(国巨)"))
      (libsource (lib "easyedapro") (part "RC0402FR-071K5L"))
    )
    (comp (ref "R42")
      (value "1.5kΩ")
      (footprint "easyedapro:R0402")
      (fields (field (name "Manufacturer Part") "RC0402FR-071K5L") (field (name "Manufacturer") "YAGEO(国巨)"))
      (libsource (lib "easyedapro") (part "RC0402FR-071K5L"))
    )
    (comp (ref "U23")
      (value "PCA9548ADGVR")
      (footprint "easyedapro:TVSOP-24_L5.0-W4.4-P0.40-LS6.4-BL")
      (fields (field (name "Manufacturer") "TI(德州仪器)"))
      (libsource (lib "easyedapro") (part "PCA9548ADGVR"))
    )
    (comp (ref "U24")
      (value "ISO1640BDR")
      (footprint "easyedapro:SOIC-8_L4.9-W3.9-P1.27-LS6.0-TL")
      (fields (field (name "Manufacturer") "TI(德州仪器)"))
      (libsource (lib "easyedapro") (part "ISO1640BDR"))
    )
  )
  (nets
    (net (code "1") (name "+3.3V_ISO_LDO") (class "Default")
      (node (ref "C11") (pin "2") (pinfunction "2_2") (pintype "unspecified"))
      (node (ref "C37") (pin "2") (pinfunction "2_2") (pintype "input"))
      (node (ref "C39") (pin "2") (pinfunction "2_2") (pintype "input"))
      (node (ref "R13") (pin "2") (pinfunction "2_2") (pintype "input"))
      (node (ref "R14") (pin "2") (pinfunction "2_2") (pintype "input"))
      (node (ref "R15") (pin "2") (pinfunction "2_2") (pintype "input"))
      (node (ref "R16") (pin "2") (pinfunction "2_2") (pintype "input"))
      (node (ref "R21") (pin "2") (pinfunction "2_2") (pintype "input"))
      (node (ref "R22") (pin "2") (pinfunction "2_2") (pintype "input"))
      (node (ref "R23") (pin "2") (pinfunction "2_2") (pintype "input"))
      (node (ref "R24") (pin "2") (pinfunction "2_2") (pintype "input"))
      (node (ref "R29") (pin "2") (pinfunction "2_2") (pintype "input"))
      (node (ref "R3") (pin "2") (pinfunction "2_2") (pintype "input"))
      (node (ref "R30") (pin "2") (pinfunction "2_2") (pintype "input"))
      (node (ref "R31") (pin "2") (pinfunction "2_2") (pintype "input"))
      (node (ref "R32") (pin "2") (pinfunction "2_2") (pintype "input"))
      (node (ref "R38") (pin "1") (pinfunction "1_1") (pintype "input"))
      (node (ref "R39") (pin "2") (pinfunction "2_2") (pintype "input"))
      (node (ref "R40") (pin "2") (pinfunction "2_2") (pintype "input"))
      (node (ref "R5") (pin "2") (pinfunction "2_2") (pintype "input"))
      (node (ref "R6") (pin "2") (pinfunction "2_2") (pintype "input"))
      (node (ref "R7") (pin "2") (pinfunction "2_2") (pintype "input"))
      (node (ref "R8") (pin "2") (pinfunction "2_2") (pintype "input"))
      (node (ref "U23") (pin "24") (pinfunction "VCC_24") (pintype "unspecified"))
      (node (ref "U24") (pin "1") (pinfunction "VCC1_1") (pintype "unspecified"))
      (node (ref "U3") (pin "5") (pinfunction "VOUT_5") (pintype "unspecified"))
    )
    (net (code "2") (name "+5V") (class "Default")
      (node (ref "C1") (pin "2") (pinfunction "2_2") (pintype "unspecified"))
      (node (ref "C2") (pin "2") (pinfunction "2_2") (pintype "input"))
      (node (ref "C35") (pin "2") (pinfunction "2_2") (pintype "input"))
      (node (ref "C38") (pin "2") (pinfunction "2_2") (pintype "input"))
      (node (ref "C5") (pin "1") (pinfunction "1_1") (pintype "unspecified"))
      (node (ref "C6") (pin "2") (pinfunction "2_2") (pintype "input"))
      (node (ref "R1") (pin "2") (pinfunction "2_2") (pintype "input"))
      (node (ref "R41") (pin "2") (pinfunction "2_2") (pintype "input"))
      (node (ref "R42") (pin "2") (pinfunction "2_2") (pintype "input"))
      (node (ref "U1") (pin "1") (pinfunction "+VIN_1") (pintype "unspecified"))
      (node (ref "U2") (pin "3") (pinfunction "VOUT_3") (pintype "unspecified"))
      (node (ref "U22") (pin "1") (pinfunction "VCC1_1") (pintype "unspecified"))
      (node (ref "U24") (pin "8") (pinfunction "VCC2_8") (pintype "unspecified"))
    )
    (net (code "3") (name "+5V_ISO") (class "Default")
      (node (ref "C10") (pin "2") (pinfunction "2_2") (pintype "unspecified"))
      (node (ref "C12") (pin "2") (pinfunction "2_2") (pintype "unspecified"))
      (node (ref "C3") (pin "2") (pinfunction "2_2") (pintype "unspecified"))
      (node (ref "C36") (pin "2") (pinfunction "2_2") (pintype "input"))
      (node (ref "C4") (pin "2") (pinfunction "2_2") (pintype "input"))
      (node (ref "L1") (pin "2") (pinfunction "2_2") (pintype "unspecified"))
      (node (ref "U22") (pin "16") (pinfunction "VCC2_16") (pintype "unspecified"))
      (node (ref "U3") (pin "1") (pinfunction "VIN_1") (pintype "unspecified"))
      (node (ref "U3") (pin "3") (pinfunction "EN_3") (pintype "unspecified"))
      (node (ref "U4") (pin "5") (pinfunction "EN_5") (pintype "unspecified"))
      (node (ref "U4") (pin "8") (pinfunction "IN_8") (pintype "unspecified"))
    )
    (net (code "4") (name "+5V_ISO_LDO") (class "Default")
      (node (ref "C13") (pin "2") (pinfunction "2_2") (pintype "input"))
      (node (ref "C14") (pin "2") (pinfunction "2_2") (pintype "input"))
      (node (ref "C15") (pin "2") (pinfunction "2_2") (pintype "input"))
      (node (ref "C16") (pin "2") (pinfunction "2_2") (pintype "input"))
      (node (ref "C17") (pin "2") (pinfunction "2_2") (pintype "input"))
      (node (ref "C18") (pin "2") (pinfunction "2_2") (pintype "input"))
      (node (ref "C19") (pin "2") (pinfunction "2_2") (pintype "input"))
      (node (ref "C20") (pin "2") (pinfunction "2_2") (pintype "input"))
      (node (ref "C21") (pin "2") (pinfunction "2_2") (pintype "input"))
      (node (ref "C22") (pin "2") (pinfunction "2_2") (pintype "input"))
      (node (ref "C23") (pin "2") (pinfunction "2_2") (pintype "input"))
      (node (ref "C24") (pin "2") (pinfunction "2_2") (pintype "input"))
      (node (ref "C25") (pin "2") (pinfunction "2_2") (pintype "input"))
      (node (ref "C26") (pin "2") (pinfunction "2_2") (pintype "input"))
      (node (ref "C27") (pin "2") (pinfunction "2_2") (pintype "input"))
      (node (ref "C28") (pin "2") (pinfunction "2_2") (pintype "input"))
      (node (ref "C29") (pin "2") (pinfunction "2_2") (pintype "input"))
      (node (ref "C30") (pin "2") (pinfunction "2_2") (pintype "input"))
      (node (ref "C31") (pin "2") (pinfunction "2_2") (pintype "unspecified"))
      (node (ref "C32") (pin "2") (pinfunction "2_2") (pintype "unspecified"))
      (node (ref "C33") (pin "2") (pinfunction "2_2") (pintype "input"))
      (node (ref "C9") (pin "2") (pinfunction "2_2") (pintype "input"))
      (node (ref "R37") (pin "2") (pinfunction "2_2") (pintype "input"))
      (node (ref "U11") (pin "13") (pinfunction "VCC_13") (pintype "unspecified"))
      (node (ref "U12") (pin "13") (pinfunction "VCC_13") (pintype "unspecified"))
      (node (ref "U15") (pin "13") (pinfunction "VCC_13") (pintype "unspecified"))
      (node (ref "U16") (pin "13") (pinfunction "VCC_13") (pintype "unspecified"))
      (node (ref "U19") (pin "13") (pinfunction "VCC_13") (pintype "unspecified"))
      (node (ref "U20") (pin "13") (pinfunction "VCC_13") (pintype "unspecified"))
      (node (ref "U21") (pin "10") (pinfunction "DVDD_10") (pintype "unspecified"))
      (node (ref "U21") (pin "7") (pinfunction "AVDD_7") (pintype "unspecified"))
      (node (ref "U4") (pin "1") (pinfunction "OUT_1") (pintype "unspecified"))
      (node (ref "U4") (pin "2") (pinfunction "FB/SNS_2") (pintype "unspecified"))
      (node (ref "U7") (pin "13") (pinfunction "VCC_13") (pintype "unspecified"))
      (node (ref "U8") (pin "13") (pinfunction "VCC_13") (pintype "unspecified"))
    )
    (net (code "5") (name "ADC_CS") (class "Default")
      (node (ref "U22") (pin "4") (pinfunction "INC_4") (pintype "unspecified"))
    )
    (net (code "6") (name "ADC_CS_ISO") (class "Default")
      (node (ref "R37") (pin "1") (pinfunction "1_1") (pintype "input"))
      (node (ref "U21") (pin "11") (pinfunction "CS#_11") (pintype "unspecified"))
      (node (ref "U22") (pin "13") (pinfunction "OUTC_13") (pintype "unspecified"))
    )
    (net (code "7") (name "ADC_SCLK") (class "Default")
      (node (ref "U22") (pin "3") (pinfunction "INB_3") (pintype "unspecified"))
    )
    (net (code "8") (name "ADC_SCLK_ISO") (class "Default")
      (node (ref "U21") (pin "13") (pinfunction "SCLK_13") (pintype "unspecified"))
      (node (ref "U22") (pin "14") (pinfunction "OUTB_14") (pintype "unspecified"))
    )
    (net (code "9") (name "ADC_SDI") (class "Default")
      (node (ref "U22") (pin "2") (pinfunction "INA_2") (pintype "unspecified"))
    )
    (net (code "10") (name "ADC_SDI_ISO") (class "Default")
      (node (ref "U21") (pin "14") (pinfunction "SDI_14") (pintype "unspecified"))
      (node (ref "U22") (pin "15") (pinfunction "OUTA_15") (pintype "unspecified"))
    )
    (net (code "11") (name "ADC_SDO") (class "Default")
      (node (ref "U22") (pin "6") (pinfunction "OUTE_6") (pintype "unspecified"))
    )
    (net (code "12") (name "ADC_SDO_ISO") (class "Default")
      (node (ref "U21") (pin "12") (pinfunction "SDO_12") (pintype "unspecified"))
      (node (ref "U22") (pin "11") (pinfunction "INE_11") (pintype "unspecified"))
    )
    (net (code "13") (name "ADL_SCL1") (class "Default")
      (node (ref "R5") (pin "1") (pinfunction "1_1") (pintype "input"))
      (node (ref "U23") (pin "5") (pinfunction "SC0_5") (pintype "unspecified"))
      (node (ref "U7") (pin "6") (pinfunction "SCL_6") (pintype "unspecified"))
    )
    (net (code "14") (name "ADL_SCL2") (class "Default")
      (node (ref "R7") (pin "1") (pinfunction "1_1") (pintype "input"))
      (node (ref "U23") (pin "7") (pinfunction "SC1_7") (pintype "unspecified"))
      (node (ref "U8") (pin "6") (pinfunction "SCL_6") (pintype "unspecified"))
    )
    (net (code "15") (name "ADL_SCL3") (class "Default")
      (node (ref "R13") (pin "1") (pinfunction "1_1") (pintype "input"))
      (node (ref "U11") (pin "6") (pinfunction "SCL_6") (pintype "unspecified"))
      (node (ref "U23") (pin "9") (pinfunction "SC2_9") (pintype "unspecified"))
    )
    (net (code "16") (name "ADL_SCL4") (class "Default")
      (node (ref "R15") (pin "1") (pinfunction "1_1") (pintype "input"))
      (node (ref "U12") (pin "6") (pinfunction "SCL_6") (pintype "unspecified"))
      (node (ref "U23") (pin "11") (pinfunction "SC3_11") (pintype "unspecified"))
    )
    (net (code "17") (name "ADL_SCL5") (class "Default")
      (node (ref "R21") (pin "1") (pinfunction "1_1") (pintype "input"))
      (node (ref "U15") (pin "6") (pinfunction "SCL_6") (pintype "unspecified"))
      (node (ref "U23") (pin "14") (pinfunction "SC4_14") (pintype "unspecified"))
    )
    (net (code "18") (name "ADL_SCL6") (class "Default")
      (node (ref "R23") (pin "1") (pinfunction "1_1") (pintype "input"))
      (node (ref "U16") (pin "6") (pinfunction "SCL_6") (pintype "unspecified"))
      (node (ref "U23") (pin "16") (pinfunction "SC5_16") (pintype "unspecified"))
    )
    (net (code "19") (name "ADL_SCL7") (class "Default")
      (node (ref "R29") (pin "1") (pinfunction "1_1") (pintype "input"))
      (node (ref "R31") (pin "1") (pinfunction "1_1") (pintype "input"))
      (node (ref "U19") (pin "6") (pinfunction "SCL_6") (pintype "unspecified"))
      (node (ref "U20") (pin "6") (pinfunction "SCL_6") (pintype "unspecified"))
      (node (ref "U23") (pin "18") (pinfunction "SC6_18") (pintype "unspecified"))
    )
    (net (code "20") (name "ADL_SCL8") (class "Default")
      (node (ref "U23") (pin "20") (pinfunction "SC7_20") (pintype "unspecified"))
    )
    (net (code "21") (name "ADL_SDA1") (class "Default")
      (node (ref "R6") (pin "1") (pinfunction "1_1") (pintype "input"))
      (node (ref "U23") (pin "4") (pinfunction "SD0_4") (pintype "unspecified"))
      (node (ref "U7") (pin "5") (pinfunction "SDA_5") (pintype "unspecified"))
    )
    (net (code "22") (name "ADL_SDA2") (class "Default")
      (node (ref "R8") (pin "1") (pinfunction "1_1") (pintype "input"))
      (node (ref "U23") (pin "6") (pinfunction "SD1_6") (pintype "unspecified"))
      (node (ref "U8") (pin "5") (pinfunction "SDA_5") (pintype "unspecified"))
    )
    (net (code "23") (name "ADL_SDA3") (class "Default")
      (node (ref "R14") (pin "1") (pinfunction "1_1") (pintype "input"))
      (node (ref "U11") (pin "5") (pinfunction "SDA_5") (pintype "unspecified"))
      (node (ref "U23") (pin "8") (pinfunction "SD2_8") (pintype "unspecified"))
    )
    (net (code "24") (name "ADL_SDA4") (class "Default")
      (node (ref "R16") (pin "1") (pinfunction "1_1") (pintype "input"))
      (node (ref "U12") (pin "5") (pinfunction "SDA_5") (pintype "unspecified"))
      (node (ref "U23") (pin "10") (pinfunction "SD3_10") (pintype "unspecified"))
    )
    (net (code "25") (name "ADL_SDA5") (class "Default")
      (node (ref "R22") (pin "1") (pinfunction "1_1") (pintype "input"))
      (node (ref "U15") (pin "5") (pinfunction "SDA_5") (pintype "unspecified"))
      (node (ref "U23") (pin "13") (pinfunction "SD4_13") (pintype "unspecified"))
    )
    (net (code "26") (name "ADL_SDA6") (class "Default")
      (node (ref "R24") (pin "1") (pinfunction "1_1") (pintype "input"))
      (node (ref "U16") (pin "5") (pinfunction "SDA_5") (pintype "unspecified"))
      (node (ref "U23") (pin "15") (pinfunction "SD5_15") (pintype "unspecified"))
    )
    (net (code "27") (name "ADL_SDA7") (class "Default")
      (node (ref "R30") (pin "1") (pinfunction "1_1") (pintype "input"))
      (node (ref "R32") (pin "1") (pinfunction "1_1") (pintype "input"))
      (node (ref "U19") (pin "5") (pinfunction "SDA_5") (pintype "unspecified"))
      (node (ref "U20") (pin "5") (pinfunction "SDA_5") (pintype "unspecified"))
      (node (ref "U23") (pin "17") (pinfunction "SD6_17") (pintype "unspecified"))
    )
    (net (code "28") (name "ADL_SDA8") (class "Default")
      (node (ref "U23") (pin "19") (pinfunction "SD7_19") (pintype "unspecified"))
    )
    (net (code "29") (name "GND") (class "Default")
      (node (ref "C1") (pin "1") (pinfunction "1_1") (pintype "unspecified"))
      (node (ref "C2") (pin "1") (pinfunction "1_1") (pintype "input"))
      (node (ref "C35") (pin "1") (pinfunction "1_1") (pintype "input"))
      (node (ref "C38") (pin "1") (pinfunction "1_1") (pintype "input"))
      (node (ref "C5") (pin "2") (pinfunction "2_2") (pintype "unspecified"))
      (node (ref "C6") (pin "1") (pinfunction "1_1") (pintype "input"))
      (node (ref "C7") (pin "1") (pinfunction "1_1") (pintype "unspecified"))
      (node (ref "C8") (pin "1") (pinfunction "1_1") (pintype "input"))
      (node (ref "DC1") (pin "2") (pinfunction "2_2") (pintype "unspecified"))
      (node (ref "DC1") (pin "3") (pinfunction "3_3") (pintype "unspecified"))
      (node (ref "R2") (pin "1") (pinfunction "1_1") (pintype "input"))
      (node (ref "U1") (pin "2") (pinfunction "-VIN_2") (pintype "unspecified"))
      (node (ref "U2") (pin "4") (pinfunction "PGND_4") (pintype "unspecified"))
      (node (ref "U22") (pin "8") (pinfunction "GND1_8") (pintype "unspecified"))
      (node (ref "U24") (pin "5") (pinfunction "GND2_5") (pintype "unspecified"))
    )
    (net (code "30") (name "GND2") (class "Default")
      (node (ref "C10") (pin "1") (pinfunction "1_1") (pintype "unspecified"))
      (node (ref "C11") (pin "1") (pinfunction "1_1") (pintype "unspecified"))
      (node (ref "C12") (pin "1") (pinfunction "1_1") (pintype "unspecified"))
      (node (ref "C13") (pin "1") (pinfunction "1_1") (pintype "input"))
      (node (ref "C14") (pin "1") (pinfunction "1_1") (pintype "input"))
      (node (ref "C15") (pin "1") (pinfunction "1_1") (pintype "input"))
      (node (ref "C16") (pin "1") (pinfunction "1_1") (pintype "input"))
      (node (ref "C17") (pin "1") (pinfunction "1_1") (pintype "input"))
      (node (ref "C18") (pin "1") (pinfunction "1_1") (pintype "input"))
      (node (ref "C19") (pin "1") (pinfunction "1_1") (pintype "input"))
      (node (ref "C20") (pin "1") (pinfunction "1_1") (pintype "input"))
      (node (ref "C21") (pin "1") (pinfunction "1_1") (pintype "input"))
      (node (ref "C22") (pin "1") (pinfunction "1_1") (pintype "input"))
      (node (ref "C23") (pin "1") (pinfunction "1_1") (pintype "input"))
      (node (ref "C24") (pin "1") (pinfunction "1_1") (pintype "input"))
      (node (ref "C25") (pin "1") (pinfunction "1_1") (pintype "input"))
      (node (ref "C26") (pin "1") (pinfunction "1_1") (pintype "input"))
      (node (ref "C27") (pin "1") (pinfunction "1_1") (pintype "input"))
      (node (ref "C28") (pin "1") (pinfunction "1_1") (pintype "input"))
      (node (ref "C29") (pin "1") (pinfunction "1_1") (pintype "input"))
      (node (ref "C3") (pin "1") (pinfunction "1_1") (pintype "unspecified"))
      (node (ref "C30") (pin "1") (pinfunction "1_1") (pintype "input"))
      (node (ref "C31") (pin "1") (pinfunction "1_1") (pintype "unspecified"))
      (node (ref "C32") (pin "1") (pinfunction "1_1") (pintype "unspecified"))
      (node (ref "C33") (pin "1") (pinfunction "1_1") (pintype "input"))
      (node (ref "C34") (pin "1") (pinfunction "1_1") (pintype "unspecified"))
      (node (ref "C36") (pin "1") (pinfunction "1_1") (pintype "input"))
      (node (ref "C37") (pin "1") (pinfunction "1_1") (pintype "input"))
      (node (ref "C39") (pin "1") (pinfunction "1_1") (pintype "input"))
      (node (ref "C4") (pin "1") (pinfunction "1_1") (pintype "input"))
      (node (ref "C9") (pin "1") (pinfunction "1_1") (pintype "input"))
      (node (ref "R11") (pin "1") (pinfunction "1_1") (pintype "input"))
      (node (ref "R12") (pin "1") (pinfunction "1_1") (pintype "input"))
      (node (ref "R19") (pin "1") (pinfunction "1_1") (pintype "input"))
      (node (ref "R20") (pin "1") (pinfunction "1_1") (pintype "input"))
      (node (ref "R27") (pin "1") (pinfunction "1_1") (pintype "input"))
      (node (ref "R28") (pin "1") (pinfunction "1_1") (pintype "input"))
      (node (ref "R35") (pin "1") (pinfunction "1_1") (pintype "input"))
      (node (ref "R36") (pin "1") (pinfunction "1_1") (pintype "input"))
      (node (ref "R4") (pin "1") (pinfunction "1_1") (pintype "input"))
      (node (ref "U1") (pin "4") (pinfunction "-VOUT_4") (pintype "unspecified"))
      (node (ref "U10") (pin "3") (pinfunction "Case_3") (pintype "unspecified"))
      (node (ref "U11") (pin "16") (pinfunction "GND_16") (pintype "unspecified"))
      (node (ref "U11") (pin "9") (pinfunction "GND_9") (pintype "unspecified"))
      (node (ref "U12") (pin "16") (pinfunction "GND_16") (pintype "unspecified"))
      (node (ref "U12") (pin "9") (pinfunction "GND_9") (pintype "unspecified"))
      (node (ref "U13") (pin "3") (pinfunction "Case_3") (pintype "unspecified"))
      (node (ref "U14") (pin "3") (pinfunction "Case_3") (pintype "unspecified"))
      (node (ref "U15") (pin "16") (pinfunction "GND_16") (pintype "unspecified"))
      (node (ref "U15") (pin "9") (pinfunction "GND_9") (pintype "unspecified"))
      (node (ref "U16") (pin "16") (pinfunction "GND_16") (pintype "unspecified"))
      (node (ref "U16") (pin "9") (pinfunction "GND_9") (pintype "unspecified"))
      (node (ref "U17") (pin "3") (pinfunction "Case_3") (pintype "unspecified"))
      (node (ref "U18") (pin "3") (pinfunction "Case_3") (pintype "unspecified"))
      (node (ref "U19") (pin "16") (pinfunction "GND_16") (pintype "unspecified"))
      (node (ref "U19") (pin "9") (pinfunction "GND_9") (pintype "unspecified"))
      (node (ref "U20") (pin "16") (pinfunction "GND_16") (pintype "unspecified"))
      (node (ref "U20") (pin "9") (pinfunction "GND_9") (pintype "unspecified"))
      (node (ref "U21") (pin "17") (pinfunction "EP_17") (pintype "unspecified"))
      (node (ref "U21") (pin "9") (pinfunction "GND_9") (pintype "unspecified"))
      (node (ref "U22") (pin "9") (pinfunction "GND2_9") (pintype "unspecified"))
      (node (ref "U23") (pin "1") (pinfunction "A0_1") (pintype "unspecified"))
      (node (ref "U23") (pin "12") (pinfunction "GND_12") (pintype "unspecified"))
      (node (ref "U23") (pin "2") (pinfunction "A1_2") (pintype "unspecified"))
      (node (ref "U23") (pin "21") (pinfunction "A2_21") (pintype "unspecified"))
      (node (ref "U24") (pin "4") (pinfunction "GND1_4") (pintype "unspecified"))
      (node (ref "U3") (pin "2") (pinfunction "GND_2") (pintype "unspecified"))
      (node (ref "U4") (pin "4") (pinfunction "GND_4") (pintype "unspecified"))
      (node (ref "U4") (pin "6") (pinfunction "GND_6") (pintype "unspecified"))
      (node (ref "U4") (pin "9") (pinfunction "EP_9") (pintype "unspecified"))
      (node (ref "U5") (pin "3") (pinfunction "Case_3") (pintype "unspecified"))
      (node (ref "U6") (pin "3") (pinfunction "Case_3") (pintype "unspecified"))
      (node (ref "U7") (pin "16") (pinfunction "GND_16") (pintype "unspecified"))
      (node (ref "U7") (pin "9") (pinfunction "GND_9") (pintype "unspecified"))
      (node (ref "U8") (pin "16") (pinfunction "GND_16") (pintype "unspecified"))
      (node (ref "U8") (pin "9") (pinfunction "GND_9") (pintype "unspecified"))
      (node (ref "U9") (pin "3") (pinfunction "Case_3") (pintype "unspecified"))
    )
    (net (code "31") (name "Net-(D1-A)") (class "Default")
      (node (ref "D1") (pin "2") (pinfunction "A_2") (pintype "unspecified"))
      (node (ref "DC1") (pin "4") (pinfunction "4_4") (pintype "unspecified"))
    )
    (net (code "32") (name "Net-(D1-K)") (class "Default")
      (node (ref "C7") (pin "2") (pinfunction "2_2") (pintype "unspecified"))
      (node (ref "C8") (pin "2") (pinfunction "2_2") (pintype "input"))
      (node (ref "D1") (pin "1") (pinfunction "K_1") (pintype "unspecified"))
      (node (ref "U2") (pin "1") (pinfunction "VIN_1") (pintype "unspecified"))
      (node (ref "U2") (pin "6") (pinfunction "EN_6") (pintype "unspecified"))
    )
    (net (code "33") (name "Net-(U1-+VOUT)") (class "Default")
      (node (ref "L1") (pin "1") (pinfunction "1_1") (pintype "unspecified"))
      (node (ref "U1") (pin "6") (pinfunction "+VOUT_6") (pintype "unspecified"))
    )
    (net (code "34") (name "Net-(U2-FB)") (class "Default")
      (node (ref "R1") (pin "1") (pinfunction "1_1") (pintype "input"))
      (node (ref "R2") (pin "2") (pinfunction "2_2") (pintype "input"))
      (node (ref "U2") (pin "7") (pinfunction "FB_7") (pintype "unspecified"))
    )
    (net (code "35") (name "Net-(U3-ADJ{slash}NC)") (class "Default")
      (node (ref "R3") (pin "1") (pinfunction "1_1") (pintype "input"))
      (node (ref "R4") (pin "2") (pinfunction "2_2") (pintype "input"))
      (node (ref "U3") (pin "4") (pinfunction "ADJ/NC_4") (pintype "unspecified"))
    )
    (net (code "36") (name "Net-(U5-ANODE)") (class "Default")
      (node (ref "U5") (pin "2") (pinfunction "ANODE_2") (pintype "unspecified"))
      (node (ref "U7") (pin "2") (pinfunction "INP_2") (pintype "unspecified"))
    )
    (net (code "37") (name "Net-(U5-CATHODE)") (class "Default")
      (node (ref "U5") (pin "1") (pinfunction "CATHODE_1") (pintype "unspecified"))
      (node (ref "U7") (pin "14") (pinfunction "PDB_14") (pintype "unspecified"))
    )
    (net (code "38") (name "Net-(U6-ANODE)") (class "Default")
      (node (ref "U6") (pin "2") (pinfunction "ANODE_2") (pintype "unspecified"))
      (node (ref "U8") (pin "2") (pinfunction "INP_2") (pintype "unspecified"))
    )
    (net (code "39") (name "Net-(U6-CATHODE)") (class "Default")
      (node (ref "U6") (pin "1") (pinfunction "CATHODE_1") (pintype "unspecified"))
      (node (ref "U8") (pin "14") (pinfunction "PDB_14") (pintype "unspecified"))
    )
    (net (code "40") (name "Net-(U7-FB)") (class "Default")
      (node (ref "R11") (pin "2") (pinfunction "2_2") (pintype "input"))
      (node (ref "R9") (pin "2") (pinfunction "2_2") (pintype "input"))
      (node (ref "U7") (pin "11") (pinfunction "FB_11") (pintype "unspecified"))
    )
    (net (code "41") (name "Net-(U7-SUM-Pad1)") (class "Default")
      (node (ref "U7") (pin "1") (pinfunction "SUM_1") (pintype "unspecified"))
      (node (ref "U7") (pin "15") (pinfunction "SUM_15") (pintype "unspecified"))
      (node (ref "U7") (pin "4") (pinfunction "SUM_4") (pintype "unspecified"))
    )
    (net (code "42") (name "Net-(U8-FB)") (class "Default")
      (node (ref "R10") (pin "2") (pinfunction "2_2") (pintype "input"))
      (node (ref "R12") (pin "2") (pinfunction "2_2") (pintype "input"))
      (node (ref "U8") (pin "11") (pinfunction "FB_11") (pintype "unspecified"))
    )
    (net (code "43") (name "Net-(U8-SUM-Pad1)") (class "Default")
      (node (ref "U8") (pin "1") (pinfunction "SUM_1") (pintype "unspecified"))
      (node (ref "U8") (pin "15") (pinfunction "SUM_15") (pintype "unspecified"))
      (node (ref "U8") (pin "4") (pinfunction "SUM_4") (pintype "unspecified"))
    )
    (net (code "44") (name "Net-(U10-ANODE)") (class "Default")
      (node (ref "U10") (pin "2") (pinfunction "ANODE_2") (pintype "unspecified"))
      (node (ref "U12") (pin "2") (pinfunction "INP_2") (pintype "unspecified"))
    )
    (net (code "45") (name "Net-(U10-CATHODE)") (class "Default")
      (node (ref "U10") (pin "1") (pinfunction "CATHODE_1") (pintype "unspecified"))
      (node (ref "U12") (pin "14") (pinfunction "PDB_14") (pintype "unspecified"))
    )
    (net (code "46") (name "Net-(U11-FB)") (class "Default")
      (node (ref "R17") (pin "2") (pinfunction "2_2") (pintype "input"))
      (node (ref "R19") (pin "2") (pinfunction "2_2") (pintype "input"))
      (node (ref "U11") (pin "11") (pinfunction "FB_11") (pintype "unspecified"))
    )
    (net (code "47") (name "Net-(U11-INP)") (class "Default")
      (node (ref "U11") (pin "2") (pinfunction "INP_2") (pintype "unspecified"))
      (node (ref "U9") (pin "2") (pinfunction "ANODE_2") (pintype "unspecified"))
    )
    (net (code "48") (name "Net-(U11-PDB)") (class "Default")
      (node (ref "U11") (pin "14") (pinfunction "PDB_14") (pintype "unspecified"))
      (node (ref "U9") (pin "1") (pinfunction "CATHODE_1") (pintype "unspecified"))
    )
    (net (code "49") (name "Net-(U11-SUM-Pad1)") (class "Default")
      (node (ref "U11") (pin "1") (pinfunction "SUM_1") (pintype "unspecified"))
      (node (ref "U11") (pin "15") (pinfunction "SUM_15") (pintype "unspecified"))
      (node (ref "U11") (pin "4") (pinfunction "SUM_4") (pintype "unspecified"))
    )
    (net (code "50") (name "Net-(U12-FB)") (class "Default")
      (node (ref "R18") (pin "2") (pinfunction "2_2") (pintype "input"))
      (node (ref "R20") (pin "2") (pinfunction "2_2") (pintype "input"))
      (node (ref "U12") (pin "11") (pinfunction "FB_11") (pintype "unspecified"))
    )
    (net (code "51") (name "Net-(U12-SUM-Pad1)") (class "Default")
      (node (ref "U12") (pin "1") (pinfunction "SUM_1") (pintype "unspecified"))
      (node (ref "U12") (pin "15") (pinfunction "SUM_15") (pintype "unspecified"))
      (node (ref "U12") (pin "4") (pinfunction "SUM_4") (pintype "unspecified"))
    )
    (net (code "52") (name "Net-(U13-ANODE)") (class "Default")
      (node (ref "U13") (pin "2") (pinfunction "ANODE_2") (pintype "unspecified"))
      (node (ref "U15") (pin "2") (pinfunction "INP_2") (pintype "unspecified"))
    )
    (net (code "53") (name "Net-(U13-CATHODE)") (class "Default")
      (node (ref "U13") (pin "1") (pinfunction "CATHODE_1") (pintype "unspecified"))
      (node (ref "U15") (pin "14") (pinfunction "PDB_14") (pintype "unspecified"))
    )
    (net (code "54") (name "Net-(U14-ANODE)") (class "Default")
      (node (ref "U14") (pin "2") (pinfunction "ANODE_2") (pintype "unspecified"))
      (node (ref "U16") (pin "2") (pinfunction "INP_2") (pintype "unspecified"))
    )
    (net (code "55") (name "Net-(U14-CATHODE)") (class "Default")
      (node (ref "U14") (pin "1") (pinfunction "CATHODE_1") (pintype "unspecified"))
      (node (ref "U16") (pin "14") (pinfunction "PDB_14") (pintype "unspecified"))
    )
    (net (code "56") (name "Net-(U15-FB)") (class "Default")
      (node (ref "R25") (pin "2") (pinfunction "2_2") (pintype "input"))
      (node (ref "R27") (pin "2") (pinfunction "2_2") (pintype "input"))
      (node (ref "U15") (pin "11") (pinfunction "FB_11") (pintype "unspecified"))
    )
    (net (code "57") (name "Net-(U15-SUM-Pad1)") (class "Default")
      (node (ref "U15") (pin "1") (pinfunction "SUM_1") (pintype "unspecified"))
      (node (ref "U15") (pin "15") (pinfunction "SUM_15") (pintype "unspecified"))
      (node (ref "U15") (pin "4") (pinfunction "SUM_4") (pintype "unspecified"))
    )
    (net (code "58") (name "Net-(U16-FB)") (class "Default")
      (node (ref "R26") (pin "2") (pinfunction "2_2") (pintype "input"))
      (node (ref "R28") (pin "2") (pinfunction "2_2") (pintype "input"))
      (node (ref "U16") (pin "11") (pinfunction "FB_11") (pintype "unspecified"))
    )
    (net (code "59") (name "Net-(U16-SUM-Pad1)") (class "Default")
      (node (ref "U16") (pin "1") (pinfunction "SUM_1") (pintype "unspecified"))
      (node (ref "U16") (pin "15") (pinfunction "SUM_15") (pintype "unspecified"))
      (node (ref "U16") (pin "4") (pinfunction "SUM_4") (pintype "unspecified"))
    )
    (net (code "60") (name "Net-(U17-ANODE)") (class "Default")
      (node (ref "U17") (pin "2") (pinfunction "ANODE_2") (pintype "unspecified"))
      (node (ref "U19") (pin "2") (pinfunction "INP_2") (pintype "unspecified"))
    )
    (net (code "61") (name "Net-(U17-CATHODE)") (class "Default")
      (node (ref "U17") (pin "1") (pinfunction "CATHODE_1") (pintype "unspecified"))
      (node (ref "U19") (pin "14") (pinfunction "PDB_14") (pintype "unspecified"))
    )
    (net (code "62") (name "Net-(U18-ANODE)") (class "Default")
      (node (ref "U18") (pin "2") (pinfunction "ANODE_2") (pintype "unspecified"))
      (node (ref "U20") (pin "2") (pinfunction "INP_2") (pintype "unspecified"))
    )
    (net (code "63") (name "Net-(U18-CATHODE)") (class "Default")
      (node (ref "U18") (pin "1") (pinfunction "CATHODE_1") (pintype "unspecified"))
      (node (ref "U20") (pin "14") (pinfunction "PDB_14") (pintype "unspecified"))
    )
    (net (code "64") (name "Net-(U19-FB)") (class "Default")
      (node (ref "R33") (pin "2") (pinfunction "2_2") (pintype "input"))
      (node (ref "R35") (pin "2") (pinfunction "2_2") (pintype "input"))
      (node (ref "U19") (pin "11") (pinfunction "FB_11") (pintype "unspecified"))
    )
    (net (code "65") (name "Net-(U19-SUM-Pad1)") (class "Default")
      (node (ref "U19") (pin "1") (pinfunction "SUM_1") (pintype "unspecified"))
      (node (ref "U19") (pin "15") (pinfunction "SUM_15") (pintype "unspecified"))
      (node (ref "U19") (pin "4") (pinfunction "SUM_4") (pintype "unspecified"))
    )
    (net (code "66") (name "Net-(U20-FB)") (class "Default")
      (node (ref "R34") (pin "2") (pinfunction "2_2") (pintype "input"))
      (node (ref "R36") (pin "2") (pinfunction "2_2") (pintype "input"))
      (node (ref "U20") (pin "11") (pinfunction "FB_11") (pintype "unspecified"))
    )
    (net (code "67") (name "Net-(U20-SUM-Pad1)") (class "Default")
      (node (ref "U20") (pin "1") (pinfunction "SUM_1") (pintype "unspecified"))
      (node (ref "U20") (pin "15") (pinfunction "SUM_15") (pintype "unspecified"))
      (node (ref "U20") (pin "4") (pinfunction "SUM_4") (pintype "unspecified"))
    )
    (net (code "68") (name "Net-(U21-REF)") (class "Default")
      (node (ref "C34") (pin "2") (pinfunction "2_2") (pintype "unspecified"))
      (node (ref "U21") (pin "8") (pinfunction "REF_8") (pintype "unspecified"))
    )
    (net (code "69") (name "Net-(U23-RESET#)") (class "Default")
      (node (ref "R38") (pin "2") (pinfunction "2_2") (pintype "input"))
      (node (ref "U23") (pin "3") (pinfunction "RESET#_3") (pintype "unspecified"))
    )
    (net (code "70") (name "PCA_SCL") (class "Default")
      (node (ref "R42") (pin "1") (pinfunction "1_1") (pintype "input"))
      (node (ref "U24") (pin "6") (pinfunction "SCL2_6") (pintype "unspecified"))
    )
    (net (code "71") (name "PCA_SCL_ISO") (class "Default")
      (node (ref "R40") (pin "1") (pinfunction "1_1") (pintype "input"))
      (node (ref "U23") (pin "22") (pinfunction "SCL_22") (pintype "unspecified"))
      (node (ref "U24") (pin "3") (pinfunction "SCL1_3") (pintype "unspecified"))
    )
    (net (code "72") (name "PCA_SDA") (class "Default")
      (node (ref "R41") (pin "1") (pinfunction "1_1") (pintype "input"))
      (node (ref "U24") (pin "7") (pinfunction "SDA2_7") (pintype "unspecified"))
    )
    (net (code "73") (name "PCA_SDA_ISO") (class "Default")
      (node (ref "R39") (pin "1") (pinfunction "1_1") (pintype "input"))
      (node (ref "U23") (pin "23") (pinfunction "SDA_23") (pintype "unspecified"))
      (node (ref "U24") (pin "2") (pinfunction "SDA1_2") (pintype "unspecified"))
    )
    (net (code "74") (name "VLOG_OUT1") (class "Default")
      (node (ref "R9") (pin "1") (pinfunction "1_1") (pintype "input"))
      (node (ref "U21") (pin "16") (pinfunction "AIN1/GPIO1_16") (pintype "unspecified"))
      (node (ref "U7") (pin "10") (pinfunction "VLOG_10") (pintype "unspecified"))
    )
    (net (code "75") (name "VLOG_OUT2") (class "Default")
      (node (ref "R10") (pin "1") (pinfunction "1_1") (pintype "input"))
      (node (ref "U21") (pin "15") (pinfunction "AIN0/GPIO0_15") (pintype "unspecified"))
      (node (ref "U8") (pin "10") (pinfunction "VLOG_10") (pintype "unspecified"))
    )
    (net (code "76") (name "VLOG_OUT3") (class "Default")
      (node (ref "R17") (pin "1") (pinfunction "1_1") (pintype "input"))
      (node (ref "U11") (pin "10") (pinfunction "VLOG_10") (pintype "unspecified"))
      (node (ref "U21") (pin "1") (pinfunction "AIN2/GPIO2_1") (pintype "unspecified"))
    )
    (net (code "77") (name "VLOG_OUT4") (class "Default")
      (node (ref "R18") (pin "1") (pinfunction "1_1") (pintype "input"))
      (node (ref "U12") (pin "10") (pinfunction "VLOG_10") (pintype "unspecified"))
      (node (ref "U21") (pin "2") (pinfunction "AIN3/GPIO3_2") (pintype "unspecified"))
    )
    (net (code "78") (name "VLOG_OUT5") (class "Default")
      (node (ref "R25") (pin "1") (pinfunction "1_1") (pintype "input"))
      (node (ref "U15") (pin "10") (pinfunction "VLOG_10") (pintype "unspecified"))
      (node (ref "U21") (pin "3") (pinfunction "AIN4/GPIO4_3") (pintype "unspecified"))
    )
    (net (code "79") (name "VLOG_OUT6") (class "Default")
      (node (ref "R26") (pin "1") (pinfunction "1_1") (pintype "input"))
      (node (ref "U16") (pin "10") (pinfunction "VLOG_10") (pintype "unspecified"))
      (node (ref "U21") (pin "4") (pinfunction "AIN5/GPIO5_4") (pintype "unspecified"))
    )
    (net (code "80") (name "VLOG_OUT7") (class "Default")
      (node (ref "R33") (pin "1") (pinfunction "1_1") (pintype "input"))
      (node (ref "U19") (pin "10") (pinfunction "VLOG_10") (pintype "unspecified"))
      (node (ref "U21") (pin "5") (pinfunction "AIN6/GPIO6_5") (pintype "unspecified"))
    )
    (net (code "81") (name "VLOG_OUT8") (class "Default")
      (node (ref "R34") (pin "1") (pinfunction "1_1") (pintype "input"))
      (node (ref "U20") (pin "10") (pinfunction "VLOG_10") (pintype "unspecified"))
      (node (ref "U21") (pin "6") (pinfunction "AIN7/GPIO7_6") (pintype "unspecified"))
    )
    (net (code "82") (name "unconnected-(U2-PG-Pad5)") (class "Default")
      (node (ref "U2") (pin "5") (pinfunction "PG_5") (pintype "unspecified"))
    )
    (net (code "83") (name "unconnected-(U2-SW-Pad2)") (class "Default")
      (node (ref "U2") (pin "2") (pinfunction "SW_2") (pintype "unspecified"))
    )
    (net (code "84") (name "unconnected-(U4-NC-Pad3)") (class "Default")
      (node (ref "U4") (pin "3") (pinfunction "NC_3") (pintype "unspecified"))
    )
    (net (code "85") (name "unconnected-(U4-NC-Pad7)") (class "Default")
      (node (ref "U4") (pin "7") (pinfunction "NC_7") (pintype "unspecified"))
    )
    (net (code "86") (name "unconnected-(U7-CMP-Pad8)") (class "Default")
      (node (ref "U7") (pin "8") (pinfunction "CMP_8") (pintype "unspecified"))
    )
    (net (code "87") (name "unconnected-(U7-CREF-Pad7)") (class "Default")
      (node (ref "U7") (pin "7") (pinfunction "CREF_7") (pintype "unspecified"))
    )
    (net (code "88") (name "unconnected-(U7-HYST-Pad12)") (class "Default")
      (node (ref "U7") (pin "12") (pinfunction "HYST_12") (pintype "unspecified"))
    )
    (net (code "89") (name "unconnected-(U7-IREF-Pad3)") (class "Default")
      (node (ref "U7") (pin "3") (pinfunction "IREF_3") (pintype "unspecified"))
    )
    (net (code "90") (name "unconnected-(U8-CMP-Pad8)") (class "Default")
      (node (ref "U8") (pin "8") (pinfunction "CMP_8") (pintype "unspecified"))
    )
    (net (code "91") (name "unconnected-(U8-CREF-Pad7)") (class "Default")
      (node (ref "U8") (pin "7") (pinfunction "CREF_7") (pintype "unspecified"))
    )
    (net (code "92") (name "unconnected-(U8-HYST-Pad12)") (class "Default")
      (node (ref "U8") (pin "12") (pinfunction "HYST_12") (pintype "unspecified"))
    )
    (net (code "93") (name "unconnected-(U8-IREF-Pad3)") (class "Default")
      (node (ref "U8") (pin "3") (pinfunction "IREF_3") (pintype "unspecified"))
    )
    (net (code "94") (name "unconnected-(U11-CMP-Pad8)") (class "Default")
      (node (ref "U11") (pin "8") (pinfunction "CMP_8") (pintype "unspecified"))
    )
    (net (code "95") (name "unconnected-(U11-CREF-Pad7)") (class "Default")
      (node (ref "U11") (pin "7") (pinfunction "CREF_7") (pintype "unspecified"))
    )
    (net (code "96") (name "unconnected-(U11-HYST-Pad12)") (class "Default")
      (node (ref "U11") (pin "12") (pinfunction "HYST_12") (pintype "unspecified"))
    )
    (net (code "97") (name "unconnected-(U11-IREF-Pad3)") (class "Default")
      (node (ref "U11") (pin "3") (pinfunction "IREF_3") (pintype "unspecified"))
    )
    (net (code "98") (name "unconnected-(U12-CMP-Pad8)") (class "Default")
      (node (ref "U12") (pin "8") (pinfunction "CMP_8") (pintype "unspecified"))
    )
    (net (code "99") (name "unconnected-(U12-CREF-Pad7)") (class "Default")
      (node (ref "U12") (pin "7") (pinfunction "CREF_7") (pintype "unspecified"))
    )
    (net (code "100") (name "unconnected-(U12-HYST-Pad12)") (class "Default")
      (node (ref "U12") (pin "12") (pinfunction "HYST_12") (pintype "unspecified"))
    )
    (net (code "101") (name "unconnected-(U12-IREF-Pad3)") (class "Default")
      (node (ref "U12") (pin "3") (pinfunction "IREF_3") (pintype "unspecified"))
    )
    (net (code "102") (name "unconnected-(U15-CMP-Pad8)") (class "Default")
      (node (ref "U15") (pin "8") (pinfunction "CMP_8") (pintype "unspecified"))
    )
    (net (code "103") (name "unconnected-(U15-CREF-Pad7)") (class "Default")
      (node (ref "U15") (pin "7") (pinfunction "CREF_7") (pintype "unspecified"))
    )
    (net (code "104") (name "unconnected-(U15-HYST-Pad12)") (class "Default")
      (node (ref "U15") (pin "12") (pinfunction "HYST_12") (pintype "unspecified"))
    )
    (net (code "105") (name "unconnected-(U15-IREF-Pad3)") (class "Default")
      (node (ref "U15") (pin "3") (pinfunction "IREF_3") (pintype "unspecified"))
    )
    (net (code "106") (name "unconnected-(U16-CMP-Pad8)") (class "Default")
      (node (ref "U16") (pin "8") (pinfunction "CMP_8") (pintype "unspecified"))
    )
    (net (code "107") (name "unconnected-(U16-CREF-Pad7)") (class "Default")
      (node (ref "U16") (pin "7") (pinfunction "CREF_7") (pintype "unspecified"))
    )
    (net (code "108") (name "unconnected-(U16-HYST-Pad12)") (class "Default")
      (node (ref "U16") (pin "12") (pinfunction "HYST_12") (pintype "unspecified"))
    )
    (net (code "109") (name "unconnected-(U16-IREF-Pad3)") (class "Default")
      (node (ref "U16") (pin "3") (pinfunction "IREF_3") (pintype "unspecified"))
    )
    (net (code "110") (name "unconnected-(U19-CMP-Pad8)") (class "Default")
      (node (ref "U19") (pin "8") (pinfunction "CMP_8") (pintype "unspecified"))
    )
    (net (code "111") (name "unconnected-(U19-CREF-Pad7)") (class "Default")
      (node (ref "U19") (pin "7") (pinfunction "CREF_7") (pintype "unspecified"))
    )
    (net (code "112") (name "unconnected-(U19-HYST-Pad12)") (class "Default")
      (node (ref "U19") (pin "12") (pinfunction "HYST_12") (pintype "unspecified"))
    )
    (net (code "113") (name "unconnected-(U19-IREF-Pad3)") (class "Default")
      (node (ref "U19") (pin "3") (pinfunction "IREF_3") (pintype "unspecified"))
    )
    (net (code "114") (name "unconnected-(U20-CMP-Pad8)") (class "Default")
      (node (ref "U20") (pin "8") (pinfunction "CMP_8") (pintype "unspecified"))
    )
    (net (code "115") (name "unconnected-(U20-CREF-Pad7)") (class "Default")
      (node (ref "U20") (pin "7") (pinfunction "CREF_7") (pintype "unspecified"))
    )
    (net (code "116") (name "unconnected-(U20-HYST-Pad12)") (class "Default")
      (node (ref "U20") (pin "12") (pinfunction "HYST_12") (pintype "unspecified"))
    )
    (net (code "117") (name "unconnected-(U20-IREF-Pad3)") (class "Default")
      (node (ref "U20") (pin "3") (pinfunction "IREF_3") (pintype "unspecified"))
    )
    (net (code "118") (name "unconnected-(U22-IND-Pad5)") (class "Default")
      (node (ref "U22") (pin "5") (pinfunction "IND_5") (pintype "unspecified"))
    )
    (net (code "119") (name "unconnected-(U22-INF-Pad10)") (class "Default")
      (node (ref "U22") (pin "10") (pinfunction "INF_10") (pintype "unspecified"))
    )
    (net (code "120") (name "unconnected-(U22-OUTD-Pad12)") (class "Default")
      (node (ref "U22") (pin "12") (pinfunction "OUTD_12") (pintype "unspecified"))
    )
    (net (code "121") (name "unconnected-(U22-OUTF-Pad7)") (class "Default")
      (node (ref "U22") (pin "7") (pinfunction "OUTF_7") (pintype "unspecified"))
    )
  )
)
